# rat.net
KiCad netlist of a schematic drawn in EAGLE
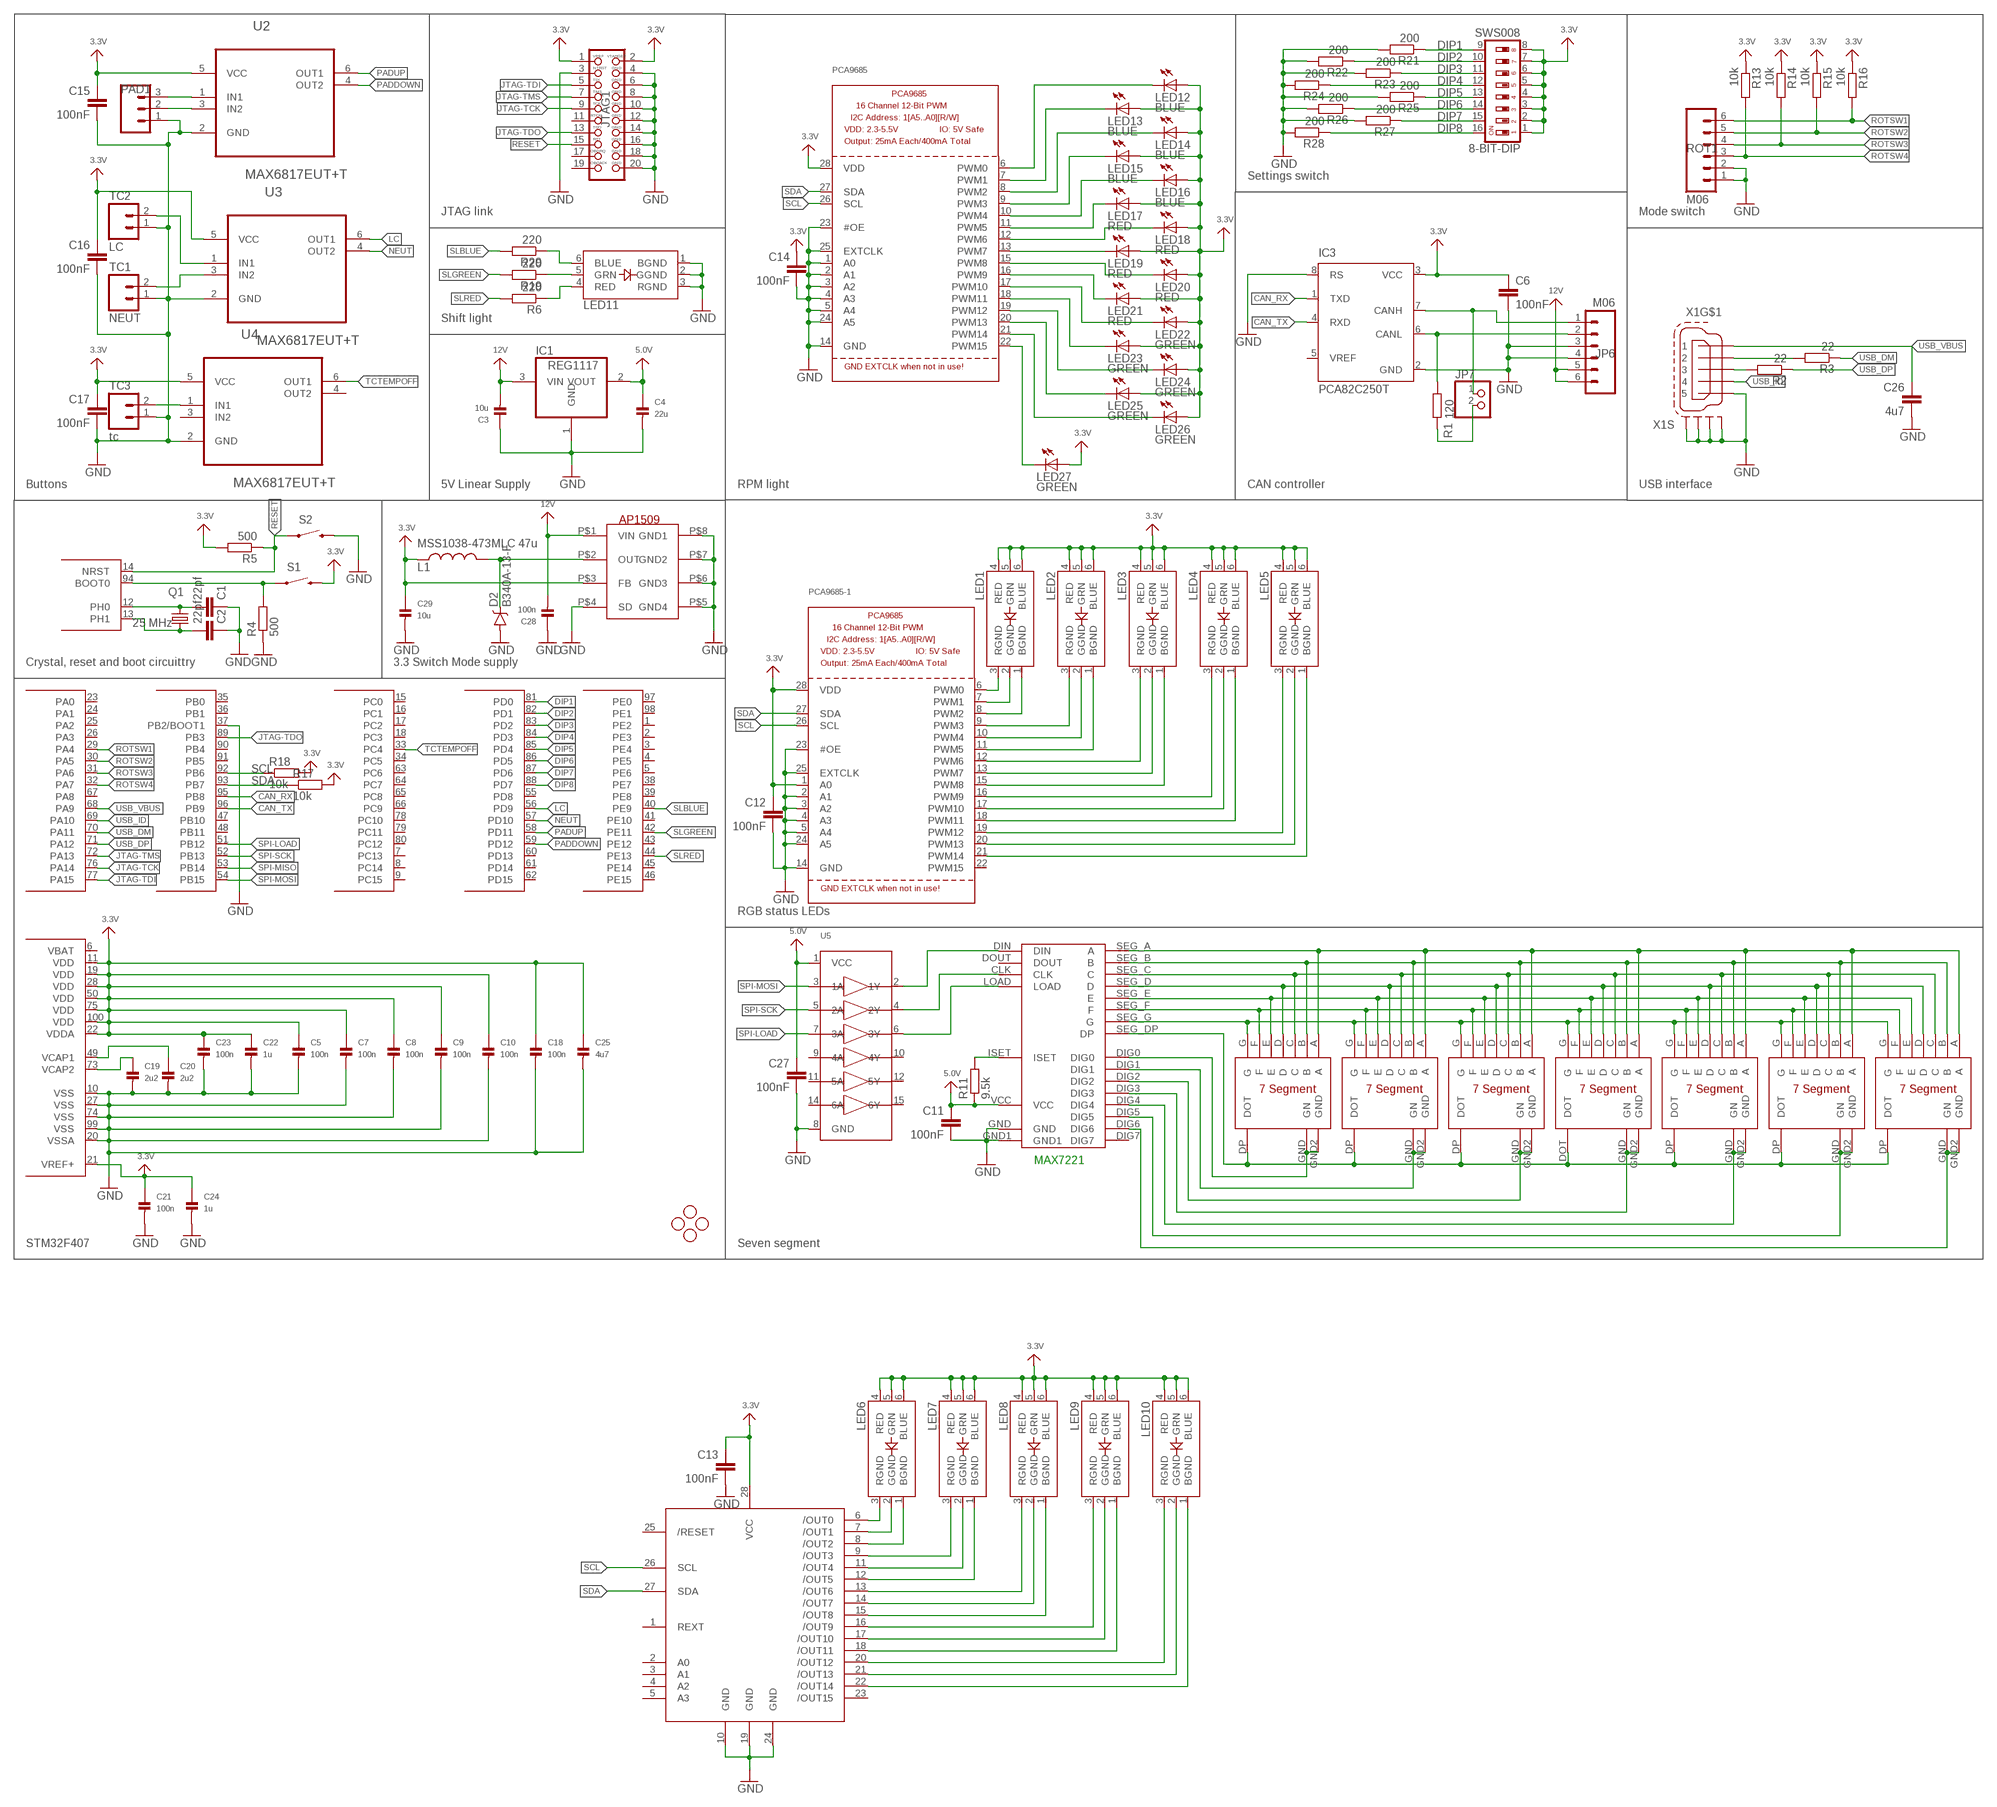
[diagram p0: schematic, sheet 1]

(export (version "E")
  (design (tool "Eeschema 10.0.6"))
  (components
    (comp (ref "8-BIT-DIP")
      (value "SWS008")
      (footprint "eagle-import:SMS-008")
      (libsource (lib "eagle-import") (part "SWS008"))
    )
    (comp (ref "C1")
      (value "22pf")
      (footprint "eagle-import:C0603K")
      (libsource (lib "eagle-import") (part "C-EUC0603K"))
    )
    (comp (ref "C2")
      (value "22pf")
      (footprint "eagle-import:C0603K")
      (libsource (lib "eagle-import") (part "C-EUC0603K"))
    )
    (comp (ref "C3")
      (value "10u")
      (footprint "eagle-import:0805")
      (libsource (lib "eagle-import") (part "CAP_CERAMIC0805"))
    )
    (comp (ref "C4")
      (value "22u")
      (footprint "eagle-import:_0603MP")
      (libsource (lib "eagle-import") (part "CAP_CERAMIC_0603MP"))
    )
    (comp (ref "C5")
      (value "100n")
      (footprint "eagle-import:_0402MP")
      (libsource (lib "eagle-import") (part "CAP_CERAMIC_0402MP"))
    )
    (comp (ref "C6")
      (value "100nF")
      (footprint "eagle-import:C0603K")
      (libsource (lib "eagle-import") (part "C-EUC0603K"))
    )
    (comp (ref "C7")
      (value "100n")
      (footprint "eagle-import:_0402MP")
      (libsource (lib "eagle-import") (part "CAP_CERAMIC_0402MP"))
    )
    (comp (ref "C8")
      (value "100n")
      (footprint "eagle-import:_0402MP")
      (libsource (lib "eagle-import") (part "CAP_CERAMIC_0402MP"))
    )
    (comp (ref "C9")
      (value "100n")
      (footprint "eagle-import:_0402MP")
      (libsource (lib "eagle-import") (part "CAP_CERAMIC_0402MP"))
    )
    (comp (ref "C10")
      (value "100n")
      (footprint "eagle-import:_0402MP")
      (libsource (lib "eagle-import") (part "CAP_CERAMIC_0402MP"))
    )
    (comp (ref "C11")
      (value "100nF")
      (footprint "eagle-import:C0603K")
      (libsource (lib "eagle-import") (part "C-EUC0603K"))
    )
    (comp (ref "C12")
      (value "100nF")
      (footprint "eagle-import:C0603K")
      (libsource (lib "eagle-import") (part "C-EUC0603K"))
    )
    (comp (ref "C13")
      (value "100nF")
      (footprint "eagle-import:C0603K")
      (libsource (lib "eagle-import") (part "C-EUC0603K"))
    )
    (comp (ref "C14")
      (value "100nF")
      (footprint "eagle-import:C0603K")
      (libsource (lib "eagle-import") (part "C-EUC0603K"))
    )
    (comp (ref "C15")
      (value "100nF")
      (footprint "eagle-import:C0603K")
      (libsource (lib "eagle-import") (part "C-EUC0603K"))
    )
    (comp (ref "C16")
      (value "100nF")
      (footprint "eagle-import:C0603K")
      (libsource (lib "eagle-import") (part "C-EUC0603K"))
    )
    (comp (ref "C17")
      (value "100nF")
      (footprint "eagle-import:C0603K")
      (libsource (lib "eagle-import") (part "C-EUC0603K"))
    )
    (comp (ref "C18")
      (value "100n")
      (footprint "eagle-import:_0402MP")
      (libsource (lib "eagle-import") (part "CAP_CERAMIC_0402MP"))
    )
    (comp (ref "C19")
      (value "2u2")
      (footprint "eagle-import:_0402MP")
      (libsource (lib "eagle-import") (part "CAP_CERAMIC_0402MP"))
    )
    (comp (ref "C20")
      (value "2u2")
      (footprint "eagle-import:_0402MP")
      (libsource (lib "eagle-import") (part "CAP_CERAMIC_0402MP"))
    )
    (comp (ref "C21")
      (value "100n")
      (footprint "eagle-import:_0402MP")
      (libsource (lib "eagle-import") (part "CAP_CERAMIC_0402MP"))
    )
    (comp (ref "C22")
      (value "1u")
      (footprint "eagle-import:_0402MP")
      (libsource (lib "eagle-import") (part "CAP_CERAMIC_0402MP"))
    )
    (comp (ref "C23")
      (value "100n")
      (footprint "eagle-import:_0402MP")
      (libsource (lib "eagle-import") (part "CAP_CERAMIC_0402MP"))
    )
    (comp (ref "C24")
      (value "1u")
      (footprint "eagle-import:_0402MP")
      (libsource (lib "eagle-import") (part "CAP_CERAMIC_0402MP"))
    )
    (comp (ref "C25")
      (value "4u7")
      (footprint "eagle-import:_0402MP")
      (libsource (lib "eagle-import") (part "CAP_CERAMIC_0402MP"))
    )
    (comp (ref "C26")
      (value "4u7")
      (footprint "eagle-import:C0603K")
      (libsource (lib "eagle-import") (part "C-EUC0603K"))
    )
    (comp (ref "C27")
      (value "100nF")
      (footprint "eagle-import:C0603K")
      (libsource (lib "eagle-import") (part "C-EUC0603K"))
    )
    (comp (ref "C28")
      (value "100n")
      (footprint "eagle-import:_0603MP")
      (libsource (lib "eagle-import") (part "CAP_CERAMIC_0603MP"))
    )
    (comp (ref "C29")
      (value "10u")
      (footprint "eagle-import:0805")
      (libsource (lib "eagle-import") (part "CAP_CERAMIC0805"))
    )
    (comp (ref "D2")
      (value "B340A-13-F")
      (footprint "eagle-import:SMA-DIODE")
      (libsource (lib "eagle-import") (part "MBRA140"))
    )
    (comp (ref "IC1")
      (value "REG1117")
      (footprint "eagle-import:SOT223")
      (libsource (lib "eagle-import") (part "REG1117"))
    )
    (comp (ref "IC3")
      (value "PCA82C250T")
      (footprint "eagle-import:SO8")
      (libsource (lib "eagle-import") (part "PCA82C250T"))
    )
    (comp (ref "JP2")
      (value "STAND-OFF")
      (footprint "eagle-import:STAND-OFF")
      (libsource (lib "eagle-import") (part "STAND-OFF"))
    )
    (comp (ref "JP3")
      (value "STAND-OFF")
      (footprint "eagle-import:STAND-OFF")
      (libsource (lib "eagle-import") (part "STAND-OFF"))
    )
    (comp (ref "JP4")
      (value "STAND-OFF")
      (footprint "eagle-import:STAND-OFF")
      (libsource (lib "eagle-import") (part "STAND-OFF"))
    )
    (comp (ref "JP5")
      (value "STAND-OFF")
      (footprint "eagle-import:STAND-OFF")
      (libsource (lib "eagle-import") (part "STAND-OFF"))
    )
    (comp (ref "JP6")
      (value "M06")
      (footprint "eagle-import:S6B_PH")
      (libsource (lib "eagle-import") (part "M06"))
    )
    (comp (ref "JP7")
      (value "PINHD-1X2/90")
      (footprint "eagle-import:1X02_90")
      (libsource (lib "eagle-import") (part "PINHD-1X2/90"))
    )
    (comp (ref "JTAG1")
      (value "JTAG-ARMEDGE")
      (footprint "eagle-import:MOLEX20_RIGHTANGLE")
      (libsource (lib "eagle-import") (part "JTAG-ARMEDGE"))
    )
    (comp (ref "L1")
      (value "MSS1038-473MLC 47u")
      (footprint "eagle-import:CDRH125")
      (libsource (lib "eagle-import") (part "INDUCTORPWR"))
    )
    (comp (ref "LED1")
      (value "LED_RGB_PLCC6CREE-CLV6A")
      (footprint "eagle-import:RGBLED_PLCC6")
      (libsource (lib "eagle-import") (part "LED_RGB_PLCC6CREE-CLV6A"))
    )
    (comp (ref "LED2")
      (value "LED_RGB_PLCC6CREE-CLV6A")
      (footprint "eagle-import:RGBLED_PLCC6")
      (libsource (lib "eagle-import") (part "LED_RGB_PLCC6CREE-CLV6A"))
    )
    (comp (ref "LED3")
      (value "LED_RGB_PLCC6CREE-CLV6A")
      (footprint "eagle-import:RGBLED_PLCC6")
      (libsource (lib "eagle-import") (part "LED_RGB_PLCC6CREE-CLV6A"))
    )
    (comp (ref "LED4")
      (value "LED_RGB_PLCC6CREE-CLV6A")
      (footprint "eagle-import:RGBLED_PLCC6")
      (libsource (lib "eagle-import") (part "LED_RGB_PLCC6CREE-CLV6A"))
    )
    (comp (ref "LED5")
      (value "LED_RGB_PLCC6CREE-CLV6A")
      (footprint "eagle-import:RGBLED_PLCC6")
      (libsource (lib "eagle-import") (part "LED_RGB_PLCC6CREE-CLV6A"))
    )
    (comp (ref "LED6")
      (value "LED_RGB_PLCC6CREE-CLV6A")
      (footprint "eagle-import:RGBLED_PLCC6")
      (libsource (lib "eagle-import") (part "LED_RGB_PLCC6CREE-CLV6A"))
    )
    (comp (ref "LED7")
      (value "LED_RGB_PLCC6CREE-CLV6A")
      (footprint "eagle-import:RGBLED_PLCC6")
      (libsource (lib "eagle-import") (part "LED_RGB_PLCC6CREE-CLV6A"))
    )
    (comp (ref "LED8")
      (value "LED_RGB_PLCC6CREE-CLV6A")
      (footprint "eagle-import:RGBLED_PLCC6")
      (libsource (lib "eagle-import") (part "LED_RGB_PLCC6CREE-CLV6A"))
    )
    (comp (ref "LED9")
      (value "LED_RGB_PLCC6CREE-CLV6A")
      (footprint "eagle-import:RGBLED_PLCC6")
      (libsource (lib "eagle-import") (part "LED_RGB_PLCC6CREE-CLV6A"))
    )
    (comp (ref "LED10")
      (value "LED_RGB_PLCC6CREE-CLV6A")
      (footprint "eagle-import:RGBLED_PLCC6")
      (libsource (lib "eagle-import") (part "LED_RGB_PLCC6CREE-CLV6A"))
    )
    (comp (ref "LED11")
      (value "LED_RGB_PLCC6CREE-CLV6A")
      (footprint "eagle-import:RGBLED_PLCC6")
      (libsource (lib "eagle-import") (part "LED_RGB_PLCC6CREE-CLV6A"))
    )
    (comp (ref "LED12")
      (value "BLUE")
      (footprint "eagle-import:1206")
      (libsource (lib "eagle-import") (part "LEDSMT1206"))
    )
    (comp (ref "LED13")
      (value "BLUE")
      (footprint "eagle-import:1206")
      (libsource (lib "eagle-import") (part "LEDSMT1206"))
    )
    (comp (ref "LED14")
      (value "BLUE")
      (footprint "eagle-import:1206")
      (libsource (lib "eagle-import") (part "LEDSMT1206"))
    )
    (comp (ref "LED15")
      (value "BLUE")
      (footprint "eagle-import:1206")
      (libsource (lib "eagle-import") (part "LEDSMT1206"))
    )
    (comp (ref "LED16")
      (value "BLUE")
      (footprint "eagle-import:1206")
      (libsource (lib "eagle-import") (part "LEDSMT1206"))
    )
    (comp (ref "LED17")
      (value "RED")
      (footprint "eagle-import:1206")
      (libsource (lib "eagle-import") (part "LEDSMT1206"))
    )
    (comp (ref "LED18")
      (value "RED")
      (footprint "eagle-import:1206")
      (libsource (lib "eagle-import") (part "LEDSMT1206"))
    )
    (comp (ref "LED19")
      (value "RED")
      (footprint "eagle-import:1206")
      (libsource (lib "eagle-import") (part "LEDSMT1206"))
    )
    (comp (ref "LED20")
      (value "RED")
      (footprint "eagle-import:1206")
      (libsource (lib "eagle-import") (part "LEDSMT1206"))
    )
    (comp (ref "LED21")
      (value "RED")
      (footprint "eagle-import:1206")
      (libsource (lib "eagle-import") (part "LEDSMT1206"))
    )
    (comp (ref "LED22")
      (value "GREEN")
      (footprint "eagle-import:1206")
      (libsource (lib "eagle-import") (part "LEDSMT1206"))
    )
    (comp (ref "LED23")
      (value "GREEN")
      (footprint "eagle-import:1206")
      (libsource (lib "eagle-import") (part "LEDSMT1206"))
    )
    (comp (ref "LED24")
      (value "GREEN")
      (footprint "eagle-import:1206")
      (libsource (lib "eagle-import") (part "LEDSMT1206"))
    )
    (comp (ref "LED25")
      (value "GREEN")
      (footprint "eagle-import:1206")
      (libsource (lib "eagle-import") (part "LEDSMT1206"))
    )
    (comp (ref "LED26")
      (value "GREEN")
      (footprint "eagle-import:1206")
      (libsource (lib "eagle-import") (part "LEDSMT1206"))
    )
    (comp (ref "LED27")
      (value "GREEN")
      (footprint "eagle-import:1206")
      (libsource (lib "eagle-import") (part "LEDSMT1206"))
    )
    (comp (ref "MAX7221")
      (value "MAX7221-SMD")
      (footprint "eagle-import:MAX7221")
      (libsource (lib "eagle-import") (part "MAX7221-SMD"))
    )
    (comp (ref "PAD1")
      (value "M03")
      (footprint "eagle-import:S3B-PH")
      (libsource (lib "eagle-import") (part "M03"))
    )
    (comp (ref "PCA9685")
      (value "PCA9685")
      (footprint "eagle-import:TSSOP28")
      (libsource (lib "eagle-import") (part "PCA9685"))
    )
    (comp (ref "PCA9685-1")
      (value "PCA9685")
      (footprint "eagle-import:TSSOP28")
      (libsource (lib "eagle-import") (part "PCA9685"))
    )
    (comp (ref "Q1")
      (value "25 MHz")
      (footprint "eagle-import:HC49U70")
      (libsource (lib "eagle-import") (part "CRYSTALHC49U70"))
    )
    (comp (ref "R1")
      (value "120")
      (footprint "eagle-import:R0603")
      (libsource (lib "eagle-import") (part "resistor_R-EU_R0603"))
    )
    (comp (ref "R2")
      (value "22")
      (footprint "eagle-import:R0603")
      (libsource (lib "eagle-import") (part "R-EU_R0603"))
    )
    (comp (ref "R3")
      (value "22")
      (footprint "eagle-import:R0603")
      (libsource (lib "eagle-import") (part "R-EU_R0603"))
    )
    (comp (ref "R4")
      (value "500")
      (footprint "eagle-import:R0603")
      (libsource (lib "eagle-import") (part "R-EU_R0603"))
    )
    (comp (ref "R5")
      (value "500")
      (footprint "eagle-import:R0603")
      (libsource (lib "eagle-import") (part "R-EU_R0603"))
    )
    (comp (ref "R6")
      (value "220")
      (footprint "eagle-import:R0603")
      (libsource (lib "eagle-import") (part "R-EU_R0603"))
    )
    (comp (ref "R11")
      (value "9.5k")
      (footprint "eagle-import:R0603")
      (libsource (lib "eagle-import") (part "R-EU_R0603"))
    )
    (comp (ref "R13")
      (value "10k")
      (footprint "eagle-import:R0603")
      (libsource (lib "eagle-import") (part "R-EU_R0603"))
    )
    (comp (ref "R14")
      (value "10k")
      (footprint "eagle-import:R0603")
      (libsource (lib "eagle-import") (part "R-EU_R0603"))
    )
    (comp (ref "R15")
      (value "10k")
      (footprint "eagle-import:R0603")
      (libsource (lib "eagle-import") (part "R-EU_R0603"))
    )
    (comp (ref "R16")
      (value "10k")
      (footprint "eagle-import:R0603")
      (libsource (lib "eagle-import") (part "R-EU_R0603"))
    )
    (comp (ref "R17")
      (value "10k")
      (footprint "eagle-import:R0603")
      (libsource (lib "eagle-import") (part "R-EU_R0603"))
    )
    (comp (ref "R18")
      (value "10k")
      (footprint "eagle-import:R0603")
      (libsource (lib "eagle-import") (part "R-EU_R0603"))
    )
    (comp (ref "R19")
      (value "220")
      (footprint "eagle-import:R0603")
      (libsource (lib "eagle-import") (part "R-EU_R0603"))
    )
    (comp (ref "R21")
      (value "200")
      (footprint "eagle-import:R0603")
      (libsource (lib "eagle-import") (part "R-EU_R0603"))
    )
    (comp (ref "R22")
      (value "200")
      (footprint "eagle-import:R0603")
      (libsource (lib "eagle-import") (part "R-EU_R0603"))
    )
    (comp (ref "R23")
      (value "200")
      (footprint "eagle-import:R0603")
      (libsource (lib "eagle-import") (part "R-EU_R0603"))
    )
    (comp (ref "R24")
      (value "200")
      (footprint "eagle-import:R0603")
      (libsource (lib "eagle-import") (part "R-EU_R0603"))
    )
    (comp (ref "R25")
      (value "200")
      (footprint "eagle-import:R0603")
      (libsource (lib "eagle-import") (part "R-EU_R0603"))
    )
    (comp (ref "R26")
      (value "200")
      (footprint "eagle-import:R0603")
      (libsource (lib "eagle-import") (part "R-EU_R0603"))
    )
    (comp (ref "R27")
      (value "200")
      (footprint "eagle-import:R0603")
      (libsource (lib "eagle-import") (part "R-EU_R0603"))
    )
    (comp (ref "R28")
      (value "200")
      (footprint "eagle-import:R0603")
      (libsource (lib "eagle-import") (part "R-EU_R0603"))
    )
    (comp (ref "R29")
      (value "220")
      (footprint "eagle-import:R0603")
      (libsource (lib "eagle-import") (part "R-EU_R0603"))
    )
    (comp (ref "ROT1")
      (value "M06")
      (footprint "eagle-import:S6B_PH")
      (libsource (lib "eagle-import") (part "M06"))
    )
    (comp (ref "S1")
      (value "SWITCH-MOMENTARY-2-SMD-1101NE")
      (footprint "eagle-import:TACTILE-SWITCH-1101NE")
      (libsource (lib "eagle-import") (part "SWITCH-MOMENTARY-2-SMD-1101NE"))
    )
    (comp (ref "S2")
      (value "SWITCH-MOMENTARY-2-SMD-1101NE")
      (footprint "eagle-import:TACTILE-SWITCH-1101NE")
      (libsource (lib "eagle-import") (part "SWITCH-MOMENTARY-2-SMD-1101NE"))
    )
    (comp (ref "TC1")
      (value "NEUT")
      (footprint "eagle-import:S2B-PH")
      (libsource (lib "eagle-import") (part "M02-JST-2MM-SMT"))
    )
    (comp (ref "TC2")
      (value "LC")
      (footprint "eagle-import:S2B-PH")
      (libsource (lib "eagle-import") (part "M02-JST-2MM-SMT"))
    )
    (comp (ref "TC3")
      (value "tc")
      (footprint "eagle-import:S2B-PH")
      (libsource (lib "eagle-import") (part "M02-JST-2MM-SMT"))
    )
    (comp (ref "U$2")
      (value "REDSEVENSEGMENT")
      (footprint "eagle-import:REDSEGMENT")
      (libsource (lib "eagle-import") (part "REDSEVENSEGMENT"))
    )
    (comp (ref "U$3")
      (value "REDSEVENSEGMENT")
      (footprint "eagle-import:REDSEGMENT")
      (libsource (lib "eagle-import") (part "REDSEVENSEGMENT"))
    )
    (comp (ref "U$4")
      (value "REDSEVENSEGMENT")
      (footprint "eagle-import:REDSEGMENT")
      (libsource (lib "eagle-import") (part "REDSEVENSEGMENT"))
    )
    (comp (ref "U$5")
      (value "BIGSEVENSEGMENT")
      (footprint "eagle-import:BIGSEVENSEGMENT")
      (libsource (lib "eagle-import") (part "BIGSEVENSEGMENT"))
    )
    (comp (ref "U$6")
      (value "REDSEVENSEGMENT")
      (footprint "eagle-import:REDSEGMENT")
      (libsource (lib "eagle-import") (part "REDSEVENSEGMENT"))
    )
    (comp (ref "U$7")
      (value "REDSEVENSEGMENT")
      (footprint "eagle-import:REDSEGMENT")
      (libsource (lib "eagle-import") (part "REDSEVENSEGMENT"))
    )
    (comp (ref "U$8")
      (value "REDSEVENSEGMENT")
      (footprint "eagle-import:REDSEGMENT")
      (libsource (lib "eagle-import") (part "REDSEVENSEGMENT"))
    )
    (comp (ref "U$10")
      (value "AP1509")
      (footprint "eagle-import:SOP-8L")
      (libsource (lib "eagle-import") (part "AP1509"))
    )
    (comp (ref "U$38")
      (value "TLC59116")
      (footprint "eagle-import:TSSOP28")
      (libsource (lib "eagle-import") (part "TLC59116"))
    )
    (comp (ref "U1")
      (value "STM32F4-100")
      (footprint "eagle-import:SQFP-S-14X14-100")
      (libsource (lib "eagle-import") (part "STM32F4-100"))
    )
    (comp (ref "U2")
      (value "MAX6817EUT+T")
      (footprint "eagle-import:SOT95P280X145-6N")
      (libsource (lib "eagle-import") (part "MAX6817EUT+T"))
    )
    (comp (ref "U3")
      (value "MAX6817EUT+T")
      (footprint "eagle-import:SOT95P280X145-6N")
      (libsource (lib "eagle-import") (part "MAX6817EUT+T"))
    )
    (comp (ref "U4")
      (value "MAX6817EUT+T")
      (footprint "eagle-import:SOT95P280X145-6N")
      (libsource (lib "eagle-import") (part "MAX6817EUT+T"))
    )
    (comp (ref "U5")
      (value "74HC4050D")
      (footprint "eagle-import:SOIC16")
      (libsource (lib "eagle-import") (part "74HC4050D"))
    )
    (comp (ref "X1")
      (value "MINI-USB-SCHIELD-32005-201")
      (footprint "eagle-import:32005-201")
      (libsource (lib "eagle-import") (part "MINI-USB-SCHIELD-32005-201"))
    )
  )
  (nets
    (net (code "1") (name "/VBAT") (class "Default")
      (node (ref "U1") (pin "6") (pinfunction "VBAT_6") (pintype "power_in"))
    )
    (net (code "2") (name "3.3V") (class "Default")
      (node (ref "8-BIT-DIP") (pin "1") (pinfunction "1_1") (pintype "passive"))
      (node (ref "8-BIT-DIP") (pin "2") (pinfunction "2_2") (pintype "passive"))
      (node (ref "8-BIT-DIP") (pin "3") (pinfunction "3_3") (pintype "passive"))
      (node (ref "8-BIT-DIP") (pin "4") (pinfunction "4_4") (pintype "passive"))
      (node (ref "8-BIT-DIP") (pin "5") (pinfunction "5_5") (pintype "passive"))
      (node (ref "8-BIT-DIP") (pin "6") (pinfunction "6_6") (pintype "passive"))
      (node (ref "8-BIT-DIP") (pin "7") (pinfunction "7_7") (pintype "passive"))
      (node (ref "8-BIT-DIP") (pin "8") (pinfunction "8_8") (pintype "passive"))
      (node (ref "C10") (pin "1") (pinfunction "P$1_1") (pintype "passive"))
      (node (ref "C12") (pin "1") (pinfunction "1_1") (pintype "passive"))
      (node (ref "C13") (pin "1") (pinfunction "1_1") (pintype "passive"))
      (node (ref "C14") (pin "1") (pinfunction "1_1") (pintype "passive"))
      (node (ref "C15") (pin "1") (pinfunction "1_1") (pintype "passive"))
      (node (ref "C16") (pin "1") (pinfunction "1_1") (pintype "passive"))
      (node (ref "C17") (pin "1") (pinfunction "1_1") (pintype "passive"))
      (node (ref "C18") (pin "1") (pinfunction "P$1_1") (pintype "passive"))
      (node (ref "C21") (pin "1") (pinfunction "P$1_1") (pintype "passive"))
      (node (ref "C22") (pin "1") (pinfunction "P$1_1") (pintype "passive"))
      (node (ref "C23") (pin "1") (pinfunction "P$1_1") (pintype "passive"))
      (node (ref "C24") (pin "1") (pinfunction "P$1_1") (pintype "passive"))
      (node (ref "C25") (pin "1") (pinfunction "P$1_1") (pintype "passive"))
      (node (ref "C29") (pin "1") (pinfunction "P$1_1") (pintype "passive"))
      (node (ref "C5") (pin "1") (pinfunction "P$1_1") (pintype "passive"))
      (node (ref "C6") (pin "1") (pinfunction "1_1") (pintype "passive"))
      (node (ref "C7") (pin "1") (pinfunction "P$1_1") (pintype "passive"))
      (node (ref "C8") (pin "1") (pinfunction "P$1_1") (pintype "passive"))
      (node (ref "C9") (pin "1") (pinfunction "P$1_1") (pintype "passive"))
      (node (ref "IC3") (pin "3") (pinfunction "VCC_3") (pintype "power_in"))
      (node (ref "JTAG1") (pin "1") (pinfunction "1_1") (pintype "passive"))
      (node (ref "JTAG1") (pin "2") (pinfunction "2_2") (pintype "passive"))
      (node (ref "L1") (pin "1") (pinfunction "1_1") (pintype "passive"))
      (node (ref "LED1") (pin "4") (pinfunction "RED_4") (pintype "bidirectional"))
      (node (ref "LED1") (pin "5") (pinfunction "GRN_5") (pintype "bidirectional"))
      (node (ref "LED1") (pin "6") (pinfunction "BLUE_6") (pintype "bidirectional"))
      (node (ref "LED10") (pin "4") (pinfunction "RED_4") (pintype "bidirectional"))
      (node (ref "LED10") (pin "5") (pinfunction "GRN_5") (pintype "bidirectional"))
      (node (ref "LED10") (pin "6") (pinfunction "BLUE_6") (pintype "bidirectional"))
      (node (ref "LED12") (pin "A") (pinfunction "A_A") (pintype "passive"))
      (node (ref "LED13") (pin "A") (pinfunction "A_A") (pintype "passive"))
      (node (ref "LED14") (pin "A") (pinfunction "A_A") (pintype "passive"))
      (node (ref "LED15") (pin "A") (pinfunction "A_A") (pintype "passive"))
      (node (ref "LED16") (pin "A") (pinfunction "A_A") (pintype "passive"))
      (node (ref "LED17") (pin "A") (pinfunction "A_A") (pintype "passive"))
      (node (ref "LED18") (pin "A") (pinfunction "A_A") (pintype "passive"))
      (node (ref "LED19") (pin "A") (pinfunction "A_A") (pintype "passive"))
      (node (ref "LED2") (pin "4") (pinfunction "RED_4") (pintype "bidirectional"))
      (node (ref "LED2") (pin "5") (pinfunction "GRN_5") (pintype "bidirectional"))
      (node (ref "LED2") (pin "6") (pinfunction "BLUE_6") (pintype "bidirectional"))
      (node (ref "LED20") (pin "A") (pinfunction "A_A") (pintype "passive"))
      (node (ref "LED21") (pin "A") (pinfunction "A_A") (pintype "passive"))
      (node (ref "LED22") (pin "A") (pinfunction "A_A") (pintype "passive"))
      (node (ref "LED23") (pin "A") (pinfunction "A_A") (pintype "passive"))
      (node (ref "LED24") (pin "A") (pinfunction "A_A") (pintype "passive"))
      (node (ref "LED25") (pin "A") (pinfunction "A_A") (pintype "passive"))
      (node (ref "LED26") (pin "A") (pinfunction "A_A") (pintype "passive"))
      (node (ref "LED27") (pin "A") (pinfunction "A_A") (pintype "passive"))
      (node (ref "LED3") (pin "4") (pinfunction "RED_4") (pintype "bidirectional"))
      (node (ref "LED3") (pin "5") (pinfunction "GRN_5") (pintype "bidirectional"))
      (node (ref "LED3") (pin "6") (pinfunction "BLUE_6") (pintype "bidirectional"))
      (node (ref "LED4") (pin "4") (pinfunction "RED_4") (pintype "bidirectional"))
      (node (ref "LED4") (pin "5") (pinfunction "GRN_5") (pintype "bidirectional"))
      (node (ref "LED4") (pin "6") (pinfunction "BLUE_6") (pintype "bidirectional"))
      (node (ref "LED5") (pin "4") (pinfunction "RED_4") (pintype "bidirectional"))
      (node (ref "LED5") (pin "5") (pinfunction "GRN_5") (pintype "bidirectional"))
      (node (ref "LED5") (pin "6") (pinfunction "BLUE_6") (pintype "bidirectional"))
      (node (ref "LED6") (pin "4") (pinfunction "RED_4") (pintype "bidirectional"))
      (node (ref "LED6") (pin "5") (pinfunction "GRN_5") (pintype "bidirectional"))
      (node (ref "LED6") (pin "6") (pinfunction "BLUE_6") (pintype "bidirectional"))
      (node (ref "LED7") (pin "4") (pinfunction "RED_4") (pintype "bidirectional"))
      (node (ref "LED7") (pin "5") (pinfunction "GRN_5") (pintype "bidirectional"))
      (node (ref "LED7") (pin "6") (pinfunction "BLUE_6") (pintype "bidirectional"))
      (node (ref "LED8") (pin "4") (pinfunction "RED_4") (pintype "bidirectional"))
      (node (ref "LED8") (pin "5") (pinfunction "GRN_5") (pintype "bidirectional"))
      (node (ref "LED8") (pin "6") (pinfunction "BLUE_6") (pintype "bidirectional"))
      (node (ref "LED9") (pin "4") (pinfunction "RED_4") (pintype "bidirectional"))
      (node (ref "LED9") (pin "5") (pinfunction "GRN_5") (pintype "bidirectional"))
      (node (ref "LED9") (pin "6") (pinfunction "BLUE_6") (pintype "bidirectional"))
      (node (ref "PCA9685") (pin "28") (pinfunction "VDD_28") (pintype "power_in"))
      (node (ref "PCA9685-1") (pin "1") (pinfunction "A0_1") (pintype "bidirectional"))
      (node (ref "PCA9685-1") (pin "28") (pinfunction "VDD_28") (pintype "power_in"))
      (node (ref "R13") (pin "1") (pinfunction "1_1") (pintype "passive"))
      (node (ref "R14") (pin "1") (pinfunction "1_1") (pintype "passive"))
      (node (ref "R15") (pin "1") (pinfunction "1_1") (pintype "passive"))
      (node (ref "R16") (pin "1") (pinfunction "1_1") (pintype "passive"))
      (node (ref "R17") (pin "2") (pinfunction "2_2") (pintype "passive"))
      (node (ref "R18") (pin "2") (pinfunction "2_2") (pintype "passive"))
      (node (ref "R5") (pin "2") (pinfunction "2_2") (pintype "passive"))
      (node (ref "S1") (pin "P$2") (pinfunction "2_P$2") (pintype "passive"))
      (node (ref "U$10") (pin "P$3") (pinfunction "FB_P$3") (pintype "bidirectional"))
      (node (ref "U$38") (pin "28") (pinfunction "VCC_28") (pintype "bidirectional"))
      (node (ref "U1") (pin "100") (pinfunction "VDD_100") (pintype "power_in"))
      (node (ref "U1") (pin "11") (pinfunction "VDD_11") (pintype "power_in"))
      (node (ref "U1") (pin "19") (pinfunction "VDD_19") (pintype "power_in"))
      (node (ref "U1") (pin "21") (pinfunction "VREF+_21") (pintype "passive"))
      (node (ref "U1") (pin "22") (pinfunction "VDDA_22") (pintype "power_in"))
      (node (ref "U1") (pin "28") (pinfunction "VDD_28") (pintype "power_in"))
      (node (ref "U1") (pin "50") (pinfunction "VDD_50") (pintype "power_in"))
      (node (ref "U1") (pin "75") (pinfunction "VDD_75") (pintype "power_in"))
      (node (ref "U2") (pin "5") (pinfunction "VCC_5") (pintype "power_in"))
      (node (ref "U3") (pin "5") (pinfunction "VCC_5") (pintype "power_in"))
      (node (ref "U4") (pin "5") (pinfunction "VCC_5") (pintype "power_in"))
    )
    (net (code "3") (name "5.0V") (class "Default")
      (node (ref "C11") (pin "1") (pinfunction "1_1") (pintype "passive"))
      (node (ref "C27") (pin "1") (pinfunction "1_1") (pintype "passive"))
      (node (ref "C4") (pin "1") (pinfunction "P$1_1") (pintype "passive"))
      (node (ref "IC1") (pin "2") (pinfunction "VOUT_2") (pintype "output"))
      (node (ref "MAX7221") (pin "VCC") (pinfunction "VCC_VCC") (pintype "bidirectional"))
      (node (ref "R11") (pin "1") (pinfunction "1_1") (pintype "passive"))
      (node (ref "U5") (pin "1") (pinfunction "VCC_1") (pintype "bidirectional"))
    )
    (net (code "4") (name "12V") (class "Default")
      (node (ref "C28") (pin "2") (pinfunction "P$2_2") (pintype "passive"))
      (node (ref "C3") (pin "2") (pinfunction "P$2_2") (pintype "passive"))
      (node (ref "IC1") (pin "3") (pinfunction "VIN_3") (pintype "input"))
      (node (ref "JP6") (pin "5") (pinfunction "5_5") (pintype "passive"))
      (node (ref "JP6") (pin "6") (pinfunction "6_6") (pintype "passive"))
      (node (ref "U$10") (pin "P$1") (pinfunction "VIN_P$1") (pintype "bidirectional"))
    )
    (net (code "5") (name "CAN_RX") (class "Default")
      (node (ref "IC3") (pin "1") (pinfunction "TXD_1") (pintype "input"))
      (node (ref "U1") (pin "95") (pinfunction "PB8_95") (pintype "bidirectional"))
    )
    (net (code "6") (name "CAN_TX") (class "Default")
      (node (ref "IC3") (pin "4") (pinfunction "RXD_4") (pintype "output"))
      (node (ref "U1") (pin "96") (pinfunction "PB9_96") (pintype "bidirectional"))
    )
    (net (code "7") (name "DIP1") (class "Default")
      (node (ref "8-BIT-DIP") (pin "9") (pinfunction "9_9") (pintype "passive"))
      (node (ref "R21") (pin "1") (pinfunction "1_1") (pintype "passive"))
      (node (ref "U1") (pin "81") (pinfunction "PD0_81") (pintype "bidirectional"))
    )
    (net (code "8") (name "DIP2") (class "Default")
      (node (ref "8-BIT-DIP") (pin "10") (pinfunction "10_10") (pintype "passive"))
      (node (ref "R22") (pin "1") (pinfunction "1_1") (pintype "passive"))
      (node (ref "U1") (pin "82") (pinfunction "PD1_82") (pintype "bidirectional"))
    )
    (net (code "9") (name "DIP3") (class "Default")
      (node (ref "8-BIT-DIP") (pin "11") (pinfunction "11_11") (pintype "passive"))
      (node (ref "R23") (pin "1") (pinfunction "1_1") (pintype "passive"))
      (node (ref "U1") (pin "83") (pinfunction "PD2_83") (pintype "bidirectional"))
    )
    (net (code "10") (name "DIP4") (class "Default")
      (node (ref "8-BIT-DIP") (pin "12") (pinfunction "12_12") (pintype "passive"))
      (node (ref "R24") (pin "1") (pinfunction "1_1") (pintype "passive"))
      (node (ref "U1") (pin "84") (pinfunction "PD3_84") (pintype "bidirectional"))
    )
    (net (code "11") (name "DIP5") (class "Default")
      (node (ref "8-BIT-DIP") (pin "13") (pinfunction "13_13") (pintype "passive"))
      (node (ref "R25") (pin "1") (pinfunction "1_1") (pintype "passive"))
      (node (ref "U1") (pin "85") (pinfunction "PD4_85") (pintype "bidirectional"))
    )
    (net (code "12") (name "DIP6") (class "Default")
      (node (ref "8-BIT-DIP") (pin "14") (pinfunction "14_14") (pintype "passive"))
      (node (ref "R26") (pin "1") (pinfunction "1_1") (pintype "passive"))
      (node (ref "U1") (pin "86") (pinfunction "PD5_86") (pintype "bidirectional"))
    )
    (net (code "13") (name "DIP7") (class "Default")
      (node (ref "8-BIT-DIP") (pin "15") (pinfunction "15_15") (pintype "passive"))
      (node (ref "R27") (pin "1") (pinfunction "1_1") (pintype "passive"))
      (node (ref "U1") (pin "87") (pinfunction "PD6_87") (pintype "bidirectional"))
    )
    (net (code "14") (name "DIP8") (class "Default")
      (node (ref "8-BIT-DIP") (pin "16") (pinfunction "16_16") (pintype "passive"))
      (node (ref "R28") (pin "1") (pinfunction "1_1") (pintype "passive"))
      (node (ref "U1") (pin "88") (pinfunction "PD7_88") (pintype "bidirectional"))
    )
    (net (code "15") (name "GND") (class "Default")
      (node (ref "C1") (pin "1") (pinfunction "1_1") (pintype "passive"))
      (node (ref "C10") (pin "2") (pinfunction "P$2_2") (pintype "passive"))
      (node (ref "C11") (pin "2") (pinfunction "2_2") (pintype "passive"))
      (node (ref "C12") (pin "2") (pinfunction "2_2") (pintype "passive"))
      (node (ref "C13") (pin "2") (pinfunction "2_2") (pintype "passive"))
      (node (ref "C14") (pin "2") (pinfunction "2_2") (pintype "passive"))
      (node (ref "C15") (pin "2") (pinfunction "2_2") (pintype "passive"))
      (node (ref "C16") (pin "2") (pinfunction "2_2") (pintype "passive"))
      (node (ref "C17") (pin "2") (pinfunction "2_2") (pintype "passive"))
      (node (ref "C18") (pin "2") (pinfunction "P$2_2") (pintype "passive"))
      (node (ref "C19") (pin "2") (pinfunction "P$2_2") (pintype "passive"))
      (node (ref "C2") (pin "1") (pinfunction "1_1") (pintype "passive"))
      (node (ref "C20") (pin "2") (pinfunction "P$2_2") (pintype "passive"))
      (node (ref "C21") (pin "2") (pinfunction "P$2_2") (pintype "passive"))
      (node (ref "C22") (pin "2") (pinfunction "P$2_2") (pintype "passive"))
      (node (ref "C23") (pin "2") (pinfunction "P$2_2") (pintype "passive"))
      (node (ref "C24") (pin "2") (pinfunction "P$2_2") (pintype "passive"))
      (node (ref "C25") (pin "2") (pinfunction "P$2_2") (pintype "passive"))
      (node (ref "C26") (pin "2") (pinfunction "2_2") (pintype "passive"))
      (node (ref "C27") (pin "2") (pinfunction "2_2") (pintype "passive"))
      (node (ref "C28") (pin "1") (pinfunction "P$1_1") (pintype "passive"))
      (node (ref "C29") (pin "2") (pinfunction "P$2_2") (pintype "passive"))
      (node (ref "C3") (pin "1") (pinfunction "P$1_1") (pintype "passive"))
      (node (ref "C4") (pin "2") (pinfunction "P$2_2") (pintype "passive"))
      (node (ref "C5") (pin "2") (pinfunction "P$2_2") (pintype "passive"))
      (node (ref "C6") (pin "2") (pinfunction "2_2") (pintype "passive"))
      (node (ref "C7") (pin "2") (pinfunction "P$2_2") (pintype "passive"))
      (node (ref "C8") (pin "2") (pinfunction "P$2_2") (pintype "passive"))
      (node (ref "C9") (pin "2") (pinfunction "P$2_2") (pintype "passive"))
      (node (ref "D2") (pin "A") (pinfunction "A_A") (pintype "passive"))
      (node (ref "IC1") (pin "1") (pinfunction "GND_1") (pintype "power_in"))
      (node (ref "IC3") (pin "2") (pinfunction "GND_2") (pintype "power_in"))
      (node (ref "IC3") (pin "8") (pinfunction "RS_8") (pintype "input"))
      (node (ref "JP6") (pin "3") (pinfunction "3_3") (pintype "passive"))
      (node (ref "JP6") (pin "4") (pinfunction "4_4") (pintype "passive"))
      (node (ref "JTAG1") (pin "10") (pinfunction "10_10") (pintype "passive"))
      (node (ref "JTAG1") (pin "12") (pinfunction "12_12") (pintype "passive"))
      (node (ref "JTAG1") (pin "14") (pinfunction "14_14") (pintype "passive"))
      (node (ref "JTAG1") (pin "16") (pinfunction "16_16") (pintype "passive"))
      (node (ref "JTAG1") (pin "18") (pinfunction "18_18") (pintype "passive"))
      (node (ref "JTAG1") (pin "20") (pinfunction "20_20") (pintype "passive"))
      (node (ref "JTAG1") (pin "3") (pinfunction "3_3") (pintype "passive"))
      (node (ref "JTAG1") (pin "4") (pinfunction "4_4") (pintype "passive"))
      (node (ref "JTAG1") (pin "6") (pinfunction "6_6") (pintype "passive"))
      (node (ref "JTAG1") (pin "8") (pinfunction "8_8") (pintype "passive"))
      (node (ref "LED11") (pin "1") (pinfunction "BGND_1") (pintype "power_in"))
      (node (ref "LED11") (pin "2") (pinfunction "GGND_2") (pintype "power_in"))
      (node (ref "LED11") (pin "3") (pinfunction "RGND_3") (pintype "power_in"))
      (node (ref "MAX7221") (pin "GND") (pinfunction "GND_GND") (pintype "bidirectional"))
      (node (ref "MAX7221") (pin "GND1") (pinfunction "GND1_GND1") (pintype "bidirectional"))
      (node (ref "PAD1") (pin "1") (pinfunction "1_1") (pintype "passive"))
      (node (ref "PCA9685") (pin "1") (pinfunction "A0_1") (pintype "bidirectional"))
      (node (ref "PCA9685") (pin "14") (pinfunction "GND_14") (pintype "power_in"))
      (node (ref "PCA9685") (pin "2") (pinfunction "A1_2") (pintype "bidirectional"))
      (node (ref "PCA9685") (pin "23") (pinfunction "#OE_23") (pintype "input"))
      (node (ref "PCA9685") (pin "24") (pinfunction "A5_24") (pintype "bidirectional"))
      (node (ref "PCA9685") (pin "25") (pinfunction "EXTCLK_25") (pintype "input"))
      (node (ref "PCA9685") (pin "3") (pinfunction "A2_3") (pintype "bidirectional"))
      (node (ref "PCA9685") (pin "4") (pinfunction "A3_4") (pintype "bidirectional"))
      (node (ref "PCA9685") (pin "5") (pinfunction "A4_5") (pintype "bidirectional"))
      (node (ref "PCA9685-1") (pin "14") (pinfunction "GND_14") (pintype "power_in"))
      (node (ref "PCA9685-1") (pin "2") (pinfunction "A1_2") (pintype "bidirectional"))
      (node (ref "PCA9685-1") (pin "23") (pinfunction "#OE_23") (pintype "input"))
      (node (ref "PCA9685-1") (pin "24") (pinfunction "A5_24") (pintype "bidirectional"))
      (node (ref "PCA9685-1") (pin "25") (pinfunction "EXTCLK_25") (pintype "input"))
      (node (ref "PCA9685-1") (pin "3") (pinfunction "A2_3") (pintype "bidirectional"))
      (node (ref "PCA9685-1") (pin "4") (pinfunction "A3_4") (pintype "bidirectional"))
      (node (ref "PCA9685-1") (pin "5") (pinfunction "A4_5") (pintype "bidirectional"))
      (node (ref "R21") (pin "2") (pinfunction "2_2") (pintype "passive"))
      (node (ref "R22") (pin "2") (pinfunction "2_2") (pintype "passive"))
      (node (ref "R23") (pin "2") (pinfunction "2_2") (pintype "passive"))
      (node (ref "R24") (pin "2") (pinfunction "2_2") (pintype "passive"))
      (node (ref "R25") (pin "2") (pinfunction "2_2") (pintype "passive"))
      (node (ref "R26") (pin "2") (pinfunction "2_2") (pintype "passive"))
      (node (ref "R27") (pin "2") (pinfunction "2_2") (pintype "passive"))
      (node (ref "R28") (pin "2") (pinfunction "2_2") (pintype "passive"))
      (node (ref "R4") (pin "1") (pinfunction "1_1") (pintype "passive"))
      (node (ref "ROT1") (pin "1") (pinfunction "1_1") (pintype "passive"))
      (node (ref "ROT1") (pin "2") (pinfunction "2_2") (pintype "passive"))
      (node (ref "S2") (pin "P$2") (pinfunction "2_P$2") (pintype "passive"))
      (node (ref "TC1") (pin "1") (pinfunction "1_1") (pintype "passive"))
      (node (ref "TC2") (pin "1") (pinfunction "1_1") (pintype "passive"))
      (node (ref "TC3") (pin "1") (pinfunction "1_1") (pintype "passive"))
      (node (ref "U$10") (pin "P$4") (pinfunction "SD_P$4") (pintype "bidirectional"))
      (node (ref "U$10") (pin "P$5") (pinfunction "GND4_P$5") (pintype "bidirectional"))
      (node (ref "U$10") (pin "P$6") (pinfunction "GND3_P$6") (pintype "bidirectional"))
      (node (ref "U$10") (pin "P$7") (pinfunction "GND2_P$7") (pintype "bidirectional"))
      (node (ref "U$10") (pin "P$8") (pinfunction "GND1_P$8") (pintype "bidirectional"))
      (node (ref "U$38") (pin "10") (pinfunction "GND_10") (pintype "bidirectional"))
      (node (ref "U$38") (pin "19") (pinfunction "GND_19") (pintype "bidirectional"))
      (node (ref "U$38") (pin "24") (pinfunction "GND_24") (pintype "bidirectional"))
      (node (ref "U1") (pin "10") (pinfunction "VSS_10") (pintype "power_in"))
      (node (ref "U1") (pin "20") (pinfunction "VSSA_20") (pintype "power_in"))
      (node (ref "U1") (pin "27") (pinfunction "VSS_27") (pintype "power_in"))
      (node (ref "U1") (pin "37") (pinfunction "PB2/BOOT1_37") (pintype "bidirectional"))
      (node (ref "U1") (pin "74") (pinfunction "VSS_74") (pintype "power_in"))
      (node (ref "U1") (pin "99") (pinfunction "VSS_99") (pintype "power_in"))
      (node (ref "U2") (pin "2") (pinfunction "GND_2") (pintype "passive"))
      (node (ref "U3") (pin "2") (pinfunction "GND_2") (pintype "passive"))
      (node (ref "U4") (pin "2") (pinfunction "GND_2") (pintype "passive"))
      (node (ref "U5") (pin "8") (pinfunction "GND_8") (pintype "bidirectional"))
      (node (ref "X1") (pin "5") (pinfunction "5_5") (pintype "passive"))
      (node (ref "X1") (pin "M1") (pinfunction "S1_M1") (pintype "passive"))
      (node (ref "X1") (pin "M2") (pinfunction "S2_M2") (pintype "passive"))
      (node (ref "X1") (pin "M3") (pinfunction "S3_M3") (pintype "passive"))
      (node (ref "X1") (pin "M4") (pinfunction "S4_M4") (pintype "passive"))
    )
    (net (code "16") (name "JTAG-TCK") (class "Default")
      (node (ref "JTAG1") (pin "9") (pinfunction "9_9") (pintype "passive"))
      (node (ref "U1") (pin "76") (pinfunction "PA14_76") (pintype "bidirectional"))
    )
    (net (code "17") (name "JTAG-TDI") (class "Default")
      (node (ref "JTAG1") (pin "5") (pinfunction "5_5") (pintype "passive"))
      (node (ref "U1") (pin "77") (pinfunction "PA15_77") (pintype "bidirectional"))
    )
    (net (code "18") (name "JTAG-TDO") (class "Default")
      (node (ref "JTAG1") (pin "13") (pinfunction "13_13") (pintype "passive"))
      (node (ref "U1") (pin "89") (pinfunction "PB3_89") (pintype "bidirectional"))
    )
    (net (code "19") (name "JTAG-TMS") (class "Default")
      (node (ref "JTAG1") (pin "7") (pinfunction "7_7") (pintype "passive"))
      (node (ref "U1") (pin "72") (pinfunction "PA13_72") (pintype "bidirectional"))
    )
    (net (code "20") (name "LC") (class "Default")
      (node (ref "U1") (pin "56") (pinfunction "PD9_56") (pintype "bidirectional"))
      (node (ref "U3") (pin "6") (pinfunction "OUT1_6") (pintype "output"))
    )
    (net (code "21") (name "NEUT") (class "Default")
      (node (ref "U1") (pin "57") (pinfunction "PD10_57") (pintype "bidirectional"))
      (node (ref "U3") (pin "4") (pinfunction "OUT2_4") (pintype "output"))
    )
    (net (code "22") (name "Net-(C19-P$1)") (class "Default")
      (node (ref "C19") (pin "1") (pinfunction "P$1_1") (pintype "passive"))
      (node (ref "U1") (pin "73") (pinfunction "VCAP2_73") (pintype "passive"))
    )
    (net (code "23") (name "Net-(C20-P$1)") (class "Default")
      (node (ref "C20") (pin "1") (pinfunction "P$1_1") (pintype "passive"))
      (node (ref "U1") (pin "49") (pinfunction "VCAP1_49") (pintype "passive"))
    )
    (net (code "24") (name "Net-(IC3-CANH)") (class "Default")
      (node (ref "IC3") (pin "7") (pinfunction "CANH_7") (pintype "bidirectional"))
      (node (ref "JP6") (pin "1") (pinfunction "1_1") (pintype "passive"))
      (node (ref "JP7") (pin "1") (pinfunction "1_1") (pintype "passive"))
    )
    (net (code "25") (name "Net-(IC3-CANL)") (class "Default")
      (node (ref "IC3") (pin "6") (pinfunction "CANL_6") (pintype "bidirectional"))
      (node (ref "JP6") (pin "2") (pinfunction "2_2") (pintype "passive"))
      (node (ref "R1") (pin "1") (pinfunction "1_1") (pintype "passive"))
    )
    (net (code "26") (name "Net-(JP7-Pad2)") (class "Default")
      (node (ref "JP7") (pin "2") (pinfunction "2_2") (pintype "passive"))
      (node (ref "R1") (pin "2") (pinfunction "2_2") (pintype "passive"))
    )
    (net (code "27") (name "Net-(LED1-BGND)") (class "Default")
      (node (ref "LED1") (pin "1") (pinfunction "BGND_1") (pintype "power_in"))
      (node (ref "PCA9685-1") (pin "8") (pinfunction "PWM2_8") (pintype "output"))
    )
    (net (code "28") (name "Net-(LED1-GGND)") (class "Default")
      (node (ref "LED1") (pin "2") (pinfunction "GGND_2") (pintype "power_in"))
      (node (ref "PCA9685-1") (pin "7") (pinfunction "PWM1_7") (pintype "output"))
    )
    (net (code "29") (name "Net-(LED1-RGND)") (class "Default")
      (node (ref "LED1") (pin "3") (pinfunction "RGND_3") (pintype "power_in"))
      (node (ref "PCA9685-1") (pin "6") (pinfunction "PWM0_6") (pintype "output"))
    )
    (net (code "30") (name "Net-(LED2-BGND)") (class "Default")
      (node (ref "LED2") (pin "1") (pinfunction "BGND_1") (pintype "power_in"))
      (node (ref "PCA9685-1") (pin "11") (pinfunction "PWM5_11") (pintype "output"))
    )
    (net (code "31") (name "Net-(LED2-GGND)") (class "Default")
      (node (ref "LED2") (pin "2") (pinfunction "GGND_2") (pintype "power_in"))
      (node (ref "PCA9685-1") (pin "10") (pinfunction "PWM4_10") (pintype "output"))
    )
    (net (code "32") (name "Net-(LED2-RGND)") (class "Default")
      (node (ref "LED2") (pin "3") (pinfunction "RGND_3") (pintype "power_in"))
      (node (ref "PCA9685-1") (pin "9") (pinfunction "PWM3_9") (pintype "output"))
    )
    (net (code "33") (name "Net-(LED3-BGND)") (class "Default")
      (node (ref "LED3") (pin "1") (pinfunction "BGND_1") (pintype "power_in"))
      (node (ref "PCA9685-1") (pin "15") (pinfunction "PWM8_15") (pintype "output"))
    )
    (net (code "34") (name "Net-(LED3-GGND)") (class "Default")
      (node (ref "LED3") (pin "2") (pinfunction "GGND_2") (pintype "power_in"))
      (node (ref "PCA9685-1") (pin "13") (pinfunction "PWM7_13") (pintype "output"))
    )
    (net (code "35") (name "Net-(LED3-RGND)") (class "Default")
      (node (ref "LED3") (pin "3") (pinfunction "RGND_3") (pintype "power_in"))
      (node (ref "PCA9685-1") (pin "12") (pinfunction "PWM6_12") (pintype "output"))
    )
    (net (code "36") (name "Net-(LED4-BGND)") (class "Default")
      (node (ref "LED4") (pin "1") (pinfunction "BGND_1") (pintype "power_in"))
      (node (ref "PCA9685-1") (pin "18") (pinfunction "PWM11_18") (pintype "output"))
    )
    (net (code "37") (name "Net-(LED4-GGND)") (class "Default")
      (node (ref "LED4") (pin "2") (pinfunction "GGND_2") (pintype "power_in"))
      (node (ref "PCA9685-1") (pin "17") (pinfunction "PWM10_17") (pintype "output"))
    )
    (net (code "38") (name "Net-(LED4-RGND)") (class "Default")
      (node (ref "LED4") (pin "3") (pinfunction "RGND_3") (pintype "power_in"))
      (node (ref "PCA9685-1") (pin "16") (pinfunction "PWM9_16") (pintype "output"))
    )
    (net (code "39") (name "Net-(LED5-BGND)") (class "Default")
      (node (ref "LED5") (pin "1") (pinfunction "BGND_1") (pintype "power_in"))
      (node (ref "PCA9685-1") (pin "21") (pinfunction "PWM14_21") (pintype "output"))
    )
    (net (code "40") (name "Net-(LED5-GGND)") (class "Default")
      (node (ref "LED5") (pin "2") (pinfunction "GGND_2") (pintype "power_in"))
      (node (ref "PCA9685-1") (pin "20") (pinfunction "PWM13_20") (pintype "output"))
    )
    (net (code "41") (name "Net-(LED5-RGND)") (class "Default")
      (node (ref "LED5") (pin "3") (pinfunction "RGND_3") (pintype "power_in"))
      (node (ref "PCA9685-1") (pin "19") (pinfunction "PWM12_19") (pintype "output"))
    )
    (net (code "42") (name "Net-(LED6-BGND)") (class "Default")
      (node (ref "LED6") (pin "1") (pinfunction "BGND_1") (pintype "power_in"))
      (node (ref "U$38") (pin "8") (pinfunction "/OUT2_8") (pintype "bidirectional"))
    )
    (net (code "43") (name "Net-(LED6-GGND)") (class "Default")
      (node (ref "LED6") (pin "2") (pinfunction "GGND_2") (pintype "power_in"))
      (node (ref "U$38") (pin "7") (pinfunction "/OUT1_7") (pintype "bidirectional"))
    )
    (net (code "44") (name "Net-(LED6-RGND)") (class "Default")
      (node (ref "LED6") (pin "3") (pinfunction "RGND_3") (pintype "power_in"))
      (node (ref "U$38") (pin "6") (pinfunction "/OUT0_6") (pintype "bidirectional"))
    )
    (net (code "45") (name "Net-(LED7-BGND)") (class "Default")
      (node (ref "LED7") (pin "1") (pinfunction "BGND_1") (pintype "power_in"))
      (node (ref "U$38") (pin "12") (pinfunction "/OUT5_12") (pintype "bidirectional"))
    )
    (net (code "46") (name "Net-(LED7-GGND)") (class "Default")
      (node (ref "LED7") (pin "2") (pinfunction "GGND_2") (pintype "power_in"))
      (node (ref "U$38") (pin "11") (pinfunction "/OUT4_11") (pintype "bidirectional"))
    )
    (net (code "47") (name "Net-(LED7-RGND)") (class "Default")
      (node (ref "LED7") (pin "3") (pinfunction "RGND_3") (pintype "power_in"))
      (node (ref "U$38") (pin "9") (pinfunction "/OUT3_9") (pintype "bidirectional"))
    )
    (net (code "48") (name "Net-(LED8-BGND)") (class "Default")
      (node (ref "LED8") (pin "1") (pinfunction "BGND_1") (pintype "power_in"))
      (node (ref "U$38") (pin "15") (pinfunction "/OUT8_15") (pintype "bidirectional"))
    )
    (net (code "49") (name "Net-(LED8-GGND)") (class "Default")
      (node (ref "LED8") (pin "2") (pinfunction "GGND_2") (pintype "power_in"))
      (node (ref "U$38") (pin "14") (pinfunction "/OUT7_14") (pintype "bidirectional"))
    )
    (net (code "50") (name "Net-(LED8-RGND)") (class "Default")
      (node (ref "LED8") (pin "3") (pinfunction "RGND_3") (pintype "power_in"))
      (node (ref "U$38") (pin "13") (pinfunction "/OUT6_13") (pintype "bidirectional"))
    )
    (net (code "51") (name "Net-(LED9-BGND)") (class "Default")
      (node (ref "LED9") (pin "1") (pinfunction "BGND_1") (pintype "power_in"))
      (node (ref "U$38") (pin "18") (pinfunction "/OUT11_18") (pintype "bidirectional"))
    )
    (net (code "52") (name "Net-(LED9-GGND)") (class "Default")
      (node (ref "LED9") (pin "2") (pinfunction "GGND_2") (pintype "power_in"))
      (node (ref "U$38") (pin "17") (pinfunction "/OUT10_17") (pintype "bidirectional"))
    )
    (net (code "53") (name "Net-(LED9-RGND)") (class "Default")
      (node (ref "LED9") (pin "3") (pinfunction "RGND_3") (pintype "power_in"))
      (node (ref "U$38") (pin "16") (pinfunction "/OUT9_16") (pintype "bidirectional"))
    )
    (net (code "54") (name "Net-(LED10-BGND)") (class "Default")
      (node (ref "LED10") (pin "1") (pinfunction "BGND_1") (pintype "power_in"))
      (node (ref "U$38") (pin "22") (pinfunction "/OUT14_22") (pintype "bidirectional"))
    )
    (net (code "55") (name "Net-(LED10-GGND)") (class "Default")
      (node (ref "LED10") (pin "2") (pinfunction "GGND_2") (pintype "power_in"))
      (node (ref "U$38") (pin "21") (pinfunction "/OUT13_21") (pintype "bidirectional"))
    )
    (net (code "56") (name "Net-(LED10-RGND)") (class "Default")
      (node (ref "LED10") (pin "3") (pinfunction "RGND_3") (pintype "power_in"))
      (node (ref "U$38") (pin "20") (pinfunction "/OUT12_20") (pintype "bidirectional"))
    )
    (net (code "57") (name "Net-(LED11-BLUE)") (class "Default")
      (node (ref "LED11") (pin "6") (pinfunction "BLUE_6") (pintype "bidirectional"))
      (node (ref "R29") (pin "1") (pinfunction "1_1") (pintype "passive"))
    )
    (net (code "58") (name "Net-(LED11-GRN)") (class "Default")
      (node (ref "LED11") (pin "5") (pinfunction "GRN_5") (pintype "bidirectional"))
      (node (ref "R19") (pin "1") (pinfunction "1_1") (pintype "passive"))
    )
    (net (code "59") (name "Net-(LED11-RED)") (class "Default")
      (node (ref "LED11") (pin "4") (pinfunction "RED_4") (pintype "bidirectional"))
      (node (ref "R6") (pin "1") (pinfunction "1_1") (pintype "passive"))
    )
    (net (code "60") (name "Net-(MAX7221-A)") (class "Default")
      (node (ref "MAX7221") (pin "SEG_A") (pinfunction "A_SEG_A") (pintype "bidirectional"))
      (node (ref "U$2") (pin "A") (pinfunction "A_A") (pintype "bidirectional"))
      (node (ref "U$3") (pin "A") (pinfunction "A_A") (pintype "bidirectional"))
      (node (ref "U$4") (pin "A") (pinfunction "A_A") (pintype "bidirectional"))
      (node (ref "U$5") (pin "A") (pinfunction "A_A") (pintype "bidirectional"))
      (node (ref "U$6") (pin "A") (pinfunction "A_A") (pintype "bidirectional"))
      (node (ref "U$7") (pin "A") (pinfunction "A_A") (pintype "bidirectional"))
      (node (ref "U$8") (pin "A") (pinfunction "A_A") (pintype "bidirectional"))
    )
    (net (code "61") (name "Net-(MAX7221-B)") (class "Default")
      (node (ref "MAX7221") (pin "SEG_B") (pinfunction "B_SEG_B") (pintype "bidirectional"))
      (node (ref "U$2") (pin "B") (pinfunction "B_B") (pintype "bidirectional"))
      (node (ref "U$3") (pin "B") (pinfunction "B_B") (pintype "bidirectional"))
      (node (ref "U$4") (pin "B") (pinfunction "B_B") (pintype "bidirectional"))
      (node (ref "U$5") (pin "B") (pinfunction "B_B") (pintype "bidirectional"))
      (node (ref "U$6") (pin "B") (pinfunction "B_B") (pintype "bidirectional"))
      (node (ref "U$7") (pin "B") (pinfunction "B_B") (pintype "bidirectional"))
      (node (ref "U$8") (pin "B") (pinfunction "B_B") (pintype "bidirectional"))
    )
    (net (code "62") (name "Net-(MAX7221-C)") (class "Default")
      (node (ref "MAX7221") (pin "SEG_C") (pinfunction "C_SEG_C") (pintype "bidirectional"))
      (node (ref "U$2") (pin "C") (pinfunction "C_C") (pintype "bidirectional"))
      (node (ref "U$3") (pin "C") (pinfunction "C_C") (pintype "bidirectional"))
      (node (ref "U$4") (pin "C") (pinfunction "C_C") (pintype "bidirectional"))
      (node (ref "U$5") (pin "C") (pinfunction "C_C") (pintype "bidirectional"))
      (node (ref "U$6") (pin "C") (pinfunction "C_C") (pintype "bidirectional"))
      (node (ref "U$7") (pin "C") (pinfunction "C_C") (pintype "bidirectional"))
      (node (ref "U$8") (pin "C") (pinfunction "C_C") (pintype "bidirectional"))
    )
    (net (code "63") (name "Net-(MAX7221-D)") (class "Default")
      (node (ref "MAX7221") (pin "SEG_D") (pinfunction "D_SEG_D") (pintype "bidirectional"))
      (node (ref "U$2") (pin "D") (pinfunction "D_D") (pintype "bidirectional"))
      (node (ref "U$3") (pin "D") (pinfunction "D_D") (pintype "bidirectional"))
      (node (ref "U$4") (pin "D") (pinfunction "D_D") (pintype "bidirectional"))
      (node (ref "U$5") (pin "D") (pinfunction "D_D") (pintype "bidirectional"))
      (node (ref "U$6") (pin "D") (pinfunction "D_D") (pintype "bidirectional"))
      (node (ref "U$7") (pin "D") (pinfunction "D_D") (pintype "bidirectional"))
      (node (ref "U$8") (pin "D") (pinfunction "D_D") (pintype "bidirectional"))
    )
    (net (code "64") (name "Net-(MAX7221-DP)") (class "Default")
      (node (ref "MAX7221") (pin "SEG_DP") (pinfunction "DP_SEG_DP") (pintype "bidirectional"))
      (node (ref "U$2") (pin "DP") (pinfunction "DOT_DP") (pintype "bidirectional"))
      (node (ref "U$3") (pin "DP") (pinfunction "DOT_DP") (pintype "bidirectional"))
      (node (ref "U$4") (pin "DP") (pinfunction "DOT_DP") (pintype "bidirectional"))
      (node (ref "U$5") (pin "DOT") (pinfunction "DOT_DOT") (pintype "bidirectional"))
      (node (ref "U$6") (pin "DP") (pinfunction "DOT_DP") (pintype "bidirectional"))
      (node (ref "U$7") (pin "DP") (pinfunction "DOT_DP") (pintype "bidirectional"))
      (node (ref "U$8") (pin "DP") (pinfunction "DOT_DP") (pintype "bidirectional"))
    )
    (net (code "65") (name "Net-(MAX7221-E)") (class "Default")
      (node (ref "MAX7221") (pin "SEG_E") (pinfunction "E_SEG_E") (pintype "bidirectional"))
      (node (ref "U$2") (pin "E") (pinfunction "E_E") (pintype "bidirectional"))
      (node (ref "U$3") (pin "E") (pinfunction "E_E") (pintype "bidirectional"))
      (node (ref "U$4") (pin "E") (pinfunction "E_E") (pintype "bidirectional"))
      (node (ref "U$5") (pin "E") (pinfunction "E_E") (pintype "bidirectional"))
      (node (ref "U$6") (pin "E") (pinfunction "E_E") (pintype "bidirectional"))
      (node (ref "U$7") (pin "E") (pinfunction "E_E") (pintype "bidirectional"))
      (node (ref "U$8") (pin "E") (pinfunction "E_E") (pintype "bidirectional"))
    )
    (net (code "66") (name "Net-(MAX7221-F)") (class "Default")
      (node (ref "MAX7221") (pin "SEG_F") (pinfunction "F_SEG_F") (pintype "bidirectional"))
      (node (ref "U$2") (pin "F") (pinfunction "F_F") (pintype "bidirectional"))
      (node (ref "U$3") (pin "F") (pinfunction "F_F") (pintype "bidirectional"))
      (node (ref "U$4") (pin "F") (pinfunction "F_F") (pintype "bidirectional"))
      (node (ref "U$5") (pin "F") (pinfunction "F_F") (pintype "bidirectional"))
      (node (ref "U$6") (pin "F") (pinfunction "F_F") (pintype "bidirectional"))
      (node (ref "U$7") (pin "F") (pinfunction "F_F") (pintype "bidirectional"))
      (node (ref "U$8") (pin "F") (pinfunction "F_F") (pintype "bidirectional"))
    )
    (net (code "67") (name "Net-(MAX7221-G)") (class "Default")
      (node (ref "MAX7221") (pin "SEG_G") (pinfunction "G_SEG_G") (pintype "bidirectional"))
      (node (ref "U$2") (pin "G") (pinfunction "G_G") (pintype "bidirectional"))
      (node (ref "U$3") (pin "G") (pinfunction "G_G") (pintype "bidirectional"))
      (node (ref "U$4") (pin "G") (pinfunction "G_G") (pintype "bidirectional"))
      (node (ref "U$5") (pin "G") (pinfunction "G_G") (pintype "bidirectional"))
      (node (ref "U$6") (pin "G") (pinfunction "G_G") (pintype "bidirectional"))
      (node (ref "U$7") (pin "G") (pinfunction "G_G") (pintype "bidirectional"))
      (node (ref "U$8") (pin "G") (pinfunction "G_G") (pintype "bidirectional"))
    )
    (net (code "68") (name "Net-(MAX7221-PadISET)") (class "Default")
      (node (ref "MAX7221") (pin "ISET") (pinfunction "ISET_ISET") (pintype "bidirectional"))
      (node (ref "R11") (pin "2") (pinfunction "2_2") (pintype "passive"))
    )
    (net (code "69") (name "Net-(PCA9685-PWM0)") (class "Default")
      (node (ref "LED12") (pin "C") (pinfunction "C_C") (pintype "passive"))
      (node (ref "PCA9685") (pin "6") (pinfunction "PWM0_6") (pintype "output"))
    )
    (net (code "70") (name "Net-(PCA9685-PWM1)") (class "Default")
      (node (ref "LED13") (pin "C") (pinfunction "C_C") (pintype "passive"))
      (node (ref "PCA9685") (pin "7") (pinfunction "PWM1_7") (pintype "output"))
    )
    (net (code "71") (name "Net-(PCA9685-PWM2)") (class "Default")
      (node (ref "LED14") (pin "C") (pinfunction "C_C") (pintype "passive"))
      (node (ref "PCA9685") (pin "8") (pinfunction "PWM2_8") (pintype "output"))
    )
    (net (code "72") (name "Net-(PCA9685-PWM3)") (class "Default")
      (node (ref "LED15") (pin "C") (pinfunction "C_C") (pintype "passive"))
      (node (ref "PCA9685") (pin "9") (pinfunction "PWM3_9") (pintype "output"))
    )
    (net (code "73") (name "Net-(PCA9685-PWM4)") (class "Default")
      (node (ref "LED16") (pin "C") (pinfunction "C_C") (pintype "passive"))
      (node (ref "PCA9685") (pin "10") (pinfunction "PWM4_10") (pintype "output"))
    )
    (net (code "74") (name "Net-(PCA9685-PWM5)") (class "Default")
      (node (ref "LED17") (pin "C") (pinfunction "C_C") (pintype "passive"))
      (node (ref "PCA9685") (pin "11") (pinfunction "PWM5_11") (pintype "output"))
    )
    (net (code "75") (name "Net-(PCA9685-PWM6)") (class "Default")
      (node (ref "LED18") (pin "C") (pinfunction "C_C") (pintype "passive"))
      (node (ref "PCA9685") (pin "12") (pinfunction "PWM6_12") (pintype "output"))
    )
    (net (code "76") (name "Net-(PCA9685-PWM7)") (class "Default")
      (node (ref "LED19") (pin "C") (pinfunction "C_C") (pintype "passive"))
      (node (ref "PCA9685") (pin "13") (pinfunction "PWM7_13") (pintype "output"))
    )
    (net (code "77") (name "Net-(PCA9685-PWM8)") (class "Default")
      (node (ref "LED20") (pin "C") (pinfunction "C_C") (pintype "passive"))
      (node (ref "PCA9685") (pin "15") (pinfunction "PWM8_15") (pintype "output"))
    )
    (net (code "78") (name "Net-(PCA9685-PWM9)") (class "Default")
      (node (ref "LED21") (pin "C") (pinfunction "C_C") (pintype "passive"))
      (node (ref "PCA9685") (pin "16") (pinfunction "PWM9_16") (pintype "output"))
    )
    (net (code "79") (name "Net-(PCA9685-PWM10)") (class "Default")
      (node (ref "LED22") (pin "C") (pinfunction "C_C") (pintype "passive"))
      (node (ref "PCA9685") (pin "17") (pinfunction "PWM10_17") (pintype "output"))
    )
    (net (code "80") (name "Net-(PCA9685-PWM11)") (class "Default")
      (node (ref "LED23") (pin "C") (pinfunction "C_C") (pintype "passive"))
      (node (ref "PCA9685") (pin "18") (pinfunction "PWM11_18") (pintype "output"))
    )
    (net (code "81") (name "Net-(PCA9685-PWM12)") (class "Default")
      (node (ref "LED24") (pin "C") (pinfunction "C_C") (pintype "passive"))
      (node (ref "PCA9685") (pin "19") (pinfunction "PWM12_19") (pintype "output"))
    )
    (net (code "82") (name "Net-(PCA9685-PWM13)") (class "Default")
      (node (ref "LED25") (pin "C") (pinfunction "C_C") (pintype "passive"))
      (node (ref "PCA9685") (pin "20") (pinfunction "PWM13_20") (pintype "output"))
    )
    (net (code "83") (name "Net-(PCA9685-PWM14)") (class "Default")
      (node (ref "LED26") (pin "C") (pinfunction "C_C") (pintype "passive"))
      (node (ref "PCA9685") (pin "21") (pinfunction "PWM14_21") (pintype "output"))
    )
    (net (code "84") (name "Net-(PCA9685-PWM15)") (class "Default")
      (node (ref "LED27") (pin "C") (pinfunction "C_C") (pintype "passive"))
      (node (ref "PCA9685") (pin "22") (pinfunction "PWM15_22") (pintype "output"))
    )
    (net (code "85") (name "Net-(R2-Pad2)") (class "Default")
      (node (ref "R2") (pin "2") (pinfunction "2_2") (pintype "passive"))
      (node (ref "X1") (pin "3") (pinfunction "3_3") (pintype "passive"))
    )
    (net (code "86") (name "Net-(R3-Pad2)") (class "Default")
      (node (ref "R3") (pin "2") (pinfunction "2_2") (pintype "passive"))
      (node (ref "X1") (pin "2") (pinfunction "2_2") (pintype "passive"))
    )
    (net (code "87") (name "Net-(S1-1)") (class "Default")
      (node (ref "R4") (pin "2") (pinfunction "2_2") (pintype "passive"))
      (node (ref "S1") (pin "P$1") (pinfunction "1_P$1") (pintype "passive"))
      (node (ref "U1") (pin "94") (pinfunction "BOOT0_94") (pintype "bidirectional"))
    )
    (net (code "88") (name "Net-(U$2-GN)") (class "Default")
      (node (ref "MAX7221") (pin "DIG0") (pinfunction "DIG0_DIG0") (pintype "bidirectional"))
      (node (ref "U$2") (pin "GND") (pinfunction "GN_GND") (pintype "bidirectional"))
      (node (ref "U$2") (pin "GND2") (pinfunction "GND_GND2") (pintype "bidirectional"))
    )
    (net (code "89") (name "Net-(U$3-GN)") (class "Default")
      (node (ref "MAX7221") (pin "DIG1") (pinfunction "DIG1_DIG1") (pintype "bidirectional"))
      (node (ref "U$3") (pin "GND") (pinfunction "GN_GND") (pintype "bidirectional"))
      (node (ref "U$3") (pin "GND2") (pinfunction "GND_GND2") (pintype "bidirectional"))
    )
    (net (code "90") (name "Net-(U$4-GN)") (class "Default")
      (node (ref "MAX7221") (pin "DIG2") (pinfunction "DIG2_DIG2") (pintype "bidirectional"))
      (node (ref "U$4") (pin "GND") (pinfunction "GN_GND") (pintype "bidirectional"))
      (node (ref "U$4") (pin "GND2") (pinfunction "GND_GND2") (pintype "bidirectional"))
    )
    (net (code "91") (name "Net-(U$5-GN)") (class "Default")
      (node (ref "MAX7221") (pin "DIG3") (pinfunction "DIG3_DIG3") (pintype "bidirectional"))
      (node (ref "U$5") (pin "GND") (pinfunction "GN_GND") (pintype "bidirectional"))
      (node (ref "U$5") (pin "GND2") (pinfunction "GND_GND2") (pintype "bidirectional"))
    )
    (net (code "92") (name "Net-(U$6-GN)") (class "Default")
      (node (ref "MAX7221") (pin "DIG4") (pinfunction "DIG4_DIG4") (pintype "bidirectional"))
      (node (ref "U$6") (pin "GND") (pinfunction "GN_GND") (pintype "bidirectional"))
      (node (ref "U$6") (pin "GND2") (pinfunction "GND_GND2") (pintype "bidirectional"))
    )
    (net (code "93") (name "Net-(U$7-GN)") (class "Default")
      (node (ref "MAX7221") (pin "DIG5") (pinfunction "DIG5_DIG5") (pintype "bidirectional"))
      (node (ref "U$7") (pin "GND") (pinfunction "GN_GND") (pintype "bidirectional"))
      (node (ref "U$7") (pin "GND2") (pinfunction "GND_GND2") (pintype "bidirectional"))
    )
    (net (code "94") (name "Net-(U$8-GN)") (class "Default")
      (node (ref "MAX7221") (pin "DIG6") (pinfunction "DIG6_DIG6") (pintype "bidirectional"))
      (node (ref "U$8") (pin "GND") (pinfunction "GN_GND") (pintype "bidirectional"))
      (node (ref "U$8") (pin "GND2") (pinfunction "GND_GND2") (pintype "bidirectional"))
    )
    (net (code "95") (name "Net-(U$10-OUT)") (class "Default")
      (node (ref "D2") (pin "C") (pinfunction "C_C") (pintype "passive"))
      (node (ref "L1") (pin "2") (pinfunction "2_2") (pintype "passive"))
      (node (ref "U$10") (pin "P$2") (pinfunction "OUT_P$2") (pintype "bidirectional"))
    )
    (net (code "96") (name "Net-(U1G-PH0)") (class "Default")
      (node (ref "C1") (pin "2") (pinfunction "2_2") (pintype "passive"))
      (node (ref "Q1") (pin "2") (pinfunction "2_2") (pintype "passive"))
      (node (ref "U1") (pin "12") (pinfunction "PH0_12") (pintype "bidirectional"))
    )
    (net (code "97") (name "Net-(U1G-PH1)") (class "Default")
      (node (ref "C2") (pin "2") (pinfunction "2_2") (pintype "passive"))
      (node (ref "Q1") (pin "1") (pinfunction "1_1") (pintype "passive"))
      (node (ref "U1") (pin "13") (pinfunction "PH1_13") (pintype "bidirectional"))
    )
    (net (code "98") (name "Net-(U2-IN1)") (class "Default")
      (node (ref "PAD1") (pin "3") (pinfunction "3_3") (pintype "passive"))
      (node (ref "U2") (pin "1") (pinfunction "IN1_1") (pintype "input"))
    )
    (net (code "99") (name "Net-(U2-IN2)") (class "Default")
      (node (ref "PAD1") (pin "2") (pinfunction "2_2") (pintype "passive"))
      (node (ref "U2") (pin "3") (pinfunction "IN2_3") (pintype "input"))
    )
    (net (code "100") (name "Net-(U3-IN1)") (class "Default")
      (node (ref "TC2") (pin "2") (pinfunction "2_2") (pintype "passive"))
      (node (ref "U3") (pin "1") (pinfunction "IN1_1") (pintype "input"))
    )
    (net (code "101") (name "Net-(U3-IN2)") (class "Default")
      (node (ref "TC1") (pin "2") (pinfunction "2_2") (pintype "passive"))
      (node (ref "U3") (pin "3") (pinfunction "IN2_3") (pintype "input"))
    )
    (net (code "102") (name "Net-(U4-IN1)") (class "Default")
      (node (ref "TC3") (pin "2") (pinfunction "2_2") (pintype "passive"))
      (node (ref "U4") (pin "1") (pinfunction "IN1_1") (pintype "input"))
    )
    (net (code "103") (name "Net-(U5-1Y)") (class "Default")
      (node (ref "MAX7221") (pin "DIN") (pinfunction "DIN_DIN") (pintype "bidirectional"))
      (node (ref "U5") (pin "2") (pinfunction "1Y_2") (pintype "bidirectional"))
    )
    (net (code "104") (name "Net-(U5-2Y)") (class "Default")
      (node (ref "MAX7221") (pin "CLK") (pinfunction "CLK_CLK") (pintype "bidirectional"))
      (node (ref "U5") (pin "4") (pinfunction "2Y_4") (pintype "bidirectional"))
    )
    (net (code "105") (name "Net-(U5-3Y)") (class "Default")
      (node (ref "MAX7221") (pin "LOAD") (pinfunction "LOAD_LOAD") (pintype "bidirectional"))
      (node (ref "U5") (pin "6") (pinfunction "3Y_6") (pintype "bidirectional"))
    )
    (net (code "106") (name "PADDOWN") (class "Default")
      (node (ref "U1") (pin "59") (pinfunction "PD12_59") (pintype "bidirectional"))
      (node (ref "U2") (pin "4") (pinfunction "OUT2_4") (pintype "output"))
    )
    (net (code "107") (name "PADUP") (class "Default")
      (node (ref "U1") (pin "58") (pinfunction "PD11_58") (pintype "bidirectional"))
      (node (ref "U2") (pin "6") (pinfunction "OUT1_6") (pintype "output"))
    )
    (net (code "108") (name "RESET") (class "Default")
      (node (ref "JTAG1") (pin "15") (pinfunction "15_15") (pintype "passive"))
      (node (ref "R5") (pin "1") (pinfunction "1_1") (pintype "passive"))
      (node (ref "S2") (pin "P$1") (pinfunction "1_P$1") (pintype "passive"))
      (node (ref "U1") (pin "14") (pinfunction "NRST_14") (pintype "bidirectional"))
    )
    (net (code "109") (name "ROTSW1") (class "Default")
      (node (ref "R16") (pin "2") (pinfunction "2_2") (pintype "passive"))
      (node (ref "ROT1") (pin "6") (pinfunction "6_6") (pintype "passive"))
      (node (ref "U1") (pin "29") (pinfunction "PA4_29") (pintype "bidirectional"))
    )
    (net (code "110") (name "ROTSW2") (class "Default")
      (node (ref "R15") (pin "2") (pinfunction "2_2") (pintype "passive"))
      (node (ref "ROT1") (pin "5") (pinfunction "5_5") (pintype "passive"))
      (node (ref "U1") (pin "30") (pinfunction "PA5_30") (pintype "bidirectional"))
    )
    (net (code "111") (name "ROTSW3") (class "Default")
      (node (ref "R14") (pin "2") (pinfunction "2_2") (pintype "passive"))
      (node (ref "ROT1") (pin "4") (pinfunction "4_4") (pintype "passive"))
      (node (ref "U1") (pin "31") (pinfunction "PA6_31") (pintype "bidirectional"))
    )
    (net (code "112") (name "ROTSW4") (class "Default")
      (node (ref "R13") (pin "2") (pinfunction "2_2") (pintype "passive"))
      (node (ref "ROT1") (pin "3") (pinfunction "3_3") (pintype "passive"))
      (node (ref "U1") (pin "32") (pinfunction "PA7_32") (pintype "bidirectional"))
    )
    (net (code "113") (name "SCL") (class "Default")
      (node (ref "PCA9685") (pin "26") (pinfunction "SCL_26") (pintype "bidirectional"))
      (node (ref "PCA9685-1") (pin "26") (pinfunction "SCL_26") (pintype "bidirectional"))
      (node (ref "R18") (pin "1") (pinfunction "1_1") (pintype "passive"))
      (node (ref "U$38") (pin "26") (pinfunction "SCL_26") (pintype "bidirectional"))
      (node (ref "U1") (pin "92") (pinfunction "PB6_92") (pintype "bidirectional"))
    )
    (net (code "114") (name "SDA") (class "Default")
      (node (ref "PCA9685") (pin "27") (pinfunction "SDA_27") (pintype "bidirectional"))
      (node (ref "PCA9685-1") (pin "27") (pinfunction "SDA_27") (pintype "bidirectional"))
      (node (ref "R17") (pin "1") (pinfunction "1_1") (pintype "passive"))
      (node (ref "U$38") (pin "27") (pinfunction "SDA_27") (pintype "bidirectional"))
      (node (ref "U1") (pin "93") (pinfunction "PB7_93") (pintype "bidirectional"))
    )
    (net (code "115") (name "SLBLUE") (class "Default")
      (node (ref "R29") (pin "2") (pinfunction "2_2") (pintype "passive"))
      (node (ref "U1") (pin "40") (pinfunction "PE9_40") (pintype "bidirectional"))
    )
    (net (code "116") (name "SLGREEN") (class "Default")
      (node (ref "R19") (pin "2") (pinfunction "2_2") (pintype "passive"))
      (node (ref "U1") (pin "42") (pinfunction "PE11_42") (pintype "bidirectional"))
    )
    (net (code "117") (name "SLRED") (class "Default")
      (node (ref "R6") (pin "2") (pinfunction "2_2") (pintype "passive"))
      (node (ref "U1") (pin "44") (pinfunction "PE13_44") (pintype "bidirectional"))
    )
    (net (code "118") (name "SPI-LOAD") (class "Default")
      (node (ref "U1") (pin "51") (pinfunction "PB12_51") (pintype "bidirectional"))
      (node (ref "U5") (pin "7") (pinfunction "3A_7") (pintype "bidirectional"))
    )
    (net (code "119") (name "SPI-MISO") (class "Default")
      (node (ref "U1") (pin "53") (pinfunction "PB14_53") (pintype "bidirectional"))
    )
    (net (code "120") (name "SPI-MOSI") (class "Default")
      (node (ref "U1") (pin "54") (pinfunction "PB15_54") (pintype "bidirectional"))
      (node (ref "U5") (pin "3") (pinfunction "1A_3") (pintype "bidirectional"))
    )
    (net (code "121") (name "SPI-SCK") (class "Default")
      (node (ref "U1") (pin "52") (pinfunction "PB13_52") (pintype "bidirectional"))
      (node (ref "U5") (pin "5") (pinfunction "2A_5") (pintype "bidirectional"))
    )
    (net (code "122") (name "TCTEMPOFF") (class "Default")
      (node (ref "U1") (pin "33") (pinfunction "PC4_33") (pintype "bidirectional"))
      (node (ref "U4") (pin "6") (pinfunction "OUT1_6") (pintype "output"))
    )
    (net (code "123") (name "USB_DM") (class "Default")
      (node (ref "R3") (pin "1") (pinfunction "1_1") (pintype "passive"))
      (node (ref "U1") (pin "70") (pinfunction "PA11_70") (pintype "bidirectional"))
    )
    (net (code "124") (name "USB_DP") (class "Default")
      (node (ref "R2") (pin "1") (pinfunction "1_1") (pintype "passive"))
      (node (ref "U1") (pin "71") (pinfunction "PA12_71") (pintype "bidirectional"))
    )
    (net (code "125") (name "USB_ID") (class "Default")
      (node (ref "U1") (pin "69") (pinfunction "PA10_69") (pintype "bidirectional"))
      (node (ref "X1") (pin "4") (pinfunction "4_4") (pintype "passive"))
    )
    (net (code "126") (name "USB_VBUS") (class "Default")
      (node (ref "C26") (pin "1") (pinfunction "1_1") (pintype "passive"))
      (node (ref "U1") (pin "68") (pinfunction "PA9_68") (pintype "bidirectional"))
      (node (ref "X1") (pin "1") (pinfunction "1_1") (pintype "passive"))
    )
    (net (code "127") (name "unconnected-(IC3-VREF-Pad5)") (class "Default")
      (node (ref "IC3") (pin "5") (pinfunction "VREF_5") (pintype "output"))
    )
    (net (code "128") (name "unconnected-(JTAG1-Pad11)") (class "Default")
      (node (ref "JTAG1") (pin "11") (pinfunction "11_11") (pintype "passive"))
    )
    (net (code "129") (name "unconnected-(JTAG1-Pad17)") (class "Default")
      (node (ref "JTAG1") (pin "17") (pinfunction "17_17") (pintype "passive"))
    )
    (net (code "130") (name "unconnected-(JTAG1-Pad19)") (class "Default")
      (node (ref "JTAG1") (pin "19") (pinfunction "19_19") (pintype "passive"))
    )
    (net (code "131") (name "unconnected-(MAX7221-PadDIG7)") (class "Default")
      (node (ref "MAX7221") (pin "DIG7") (pinfunction "DIG7_DIG7") (pintype "bidirectional"))
    )
    (net (code "132") (name "unconnected-(MAX7221-PadDOUT)") (class "Default")
      (node (ref "MAX7221") (pin "DOUT") (pinfunction "DOUT_DOUT") (pintype "bidirectional"))
    )
    (net (code "133") (name "unconnected-(PCA9685-1-PWM15-Pad22)") (class "Default")
      (node (ref "PCA9685-1") (pin "22") (pinfunction "PWM15_22") (pintype "output"))
    )
    (net (code "134") (name "unconnected-(U$38-A0-Pad2)") (class "Default")
      (node (ref "U$38") (pin "2") (pinfunction "A0_2") (pintype "bidirectional"))
    )
    (net (code "135") (name "unconnected-(U$38-A1-Pad3)") (class "Default")
      (node (ref "U$38") (pin "3") (pinfunction "A1_3") (pintype "bidirectional"))
    )
    (net (code "136") (name "unconnected-(U$38-A2-Pad4)") (class "Default")
      (node (ref "U$38") (pin "4") (pinfunction "A2_4") (pintype "bidirectional"))
    )
    (net (code "137") (name "unconnected-(U$38-A3-Pad5)") (class "Default")
      (node (ref "U$38") (pin "5") (pinfunction "A3_5") (pintype "bidirectional"))
    )
    (net (code "138") (name "unconnected-(U$38-REXT-Pad1)") (class "Default")
      (node (ref "U$38") (pin "1") (pinfunction "REXT_1") (pintype "bidirectional"))
    )
    (net (code "139") (name "unconnected-(U$38-{slash}OUT15-Pad23)") (class "Default")
      (node (ref "U$38") (pin "23") (pinfunction "/OUT15_23") (pintype "bidirectional"))
    )
    (net (code "140") (name "unconnected-(U$38-{slash}RESET-Pad25)") (class "Default")
      (node (ref "U$38") (pin "25") (pinfunction "/RESET_25") (pintype "bidirectional"))
    )
    (net (code "141") (name "unconnected-(U1B-PA0-Pad23)") (class "Default")
      (node (ref "U1") (pin "23") (pinfunction "PA0_23") (pintype "bidirectional"))
    )
    (net (code "142") (name "unconnected-(U1B-PA1-Pad24)") (class "Default")
      (node (ref "U1") (pin "24") (pinfunction "PA1_24") (pintype "bidirectional"))
    )
    (net (code "143") (name "unconnected-(U1B-PA2-Pad25)") (class "Default")
      (node (ref "U1") (pin "25") (pinfunction "PA2_25") (pintype "bidirectional"))
    )
    (net (code "144") (name "unconnected-(U1B-PA3-Pad26)") (class "Default")
      (node (ref "U1") (pin "26") (pinfunction "PA3_26") (pintype "bidirectional"))
    )
    (net (code "145") (name "unconnected-(U1B-PA8-Pad67)") (class "Default")
      (node (ref "U1") (pin "67") (pinfunction "PA8_67") (pintype "bidirectional"))
    )
    (net (code "146") (name "unconnected-(U1C-PB0-Pad35)") (class "Default")
      (node (ref "U1") (pin "35") (pinfunction "PB0_35") (pintype "bidirectional"))
    )
    (net (code "147") (name "unconnected-(U1C-PB1-Pad36)") (class "Default")
      (node (ref "U1") (pin "36") (pinfunction "PB1_36") (pintype "bidirectional"))
    )
    (net (code "148") (name "unconnected-(U1C-PB4-Pad90)") (class "Default")
      (node (ref "U1") (pin "90") (pinfunction "PB4_90") (pintype "bidirectional"))
    )
    (net (code "149") (name "unconnected-(U1C-PB5-Pad91)") (class "Default")
      (node (ref "U1") (pin "91") (pinfunction "PB5_91") (pintype "bidirectional"))
    )
    (net (code "150") (name "unconnected-(U1C-PB10-Pad47)") (class "Default")
      (node (ref "U1") (pin "47") (pinfunction "PB10_47") (pintype "bidirectional"))
    )
    (net (code "151") (name "unconnected-(U1C-PB11-Pad48)") (class "Default")
      (node (ref "U1") (pin "48") (pinfunction "PB11_48") (pintype "bidirectional"))
    )
    (net (code "152") (name "unconnected-(U1D-PC0-Pad15)") (class "Default")
      (node (ref "U1") (pin "15") (pinfunction "PC0_15") (pintype "bidirectional"))
    )
    (net (code "153") (name "unconnected-(U1D-PC1-Pad16)") (class "Default")
      (node (ref "U1") (pin "16") (pinfunction "PC1_16") (pintype "bidirectional"))
    )
    (net (code "154") (name "unconnected-(U1D-PC2-Pad17)") (class "Default")
      (node (ref "U1") (pin "17") (pinfunction "PC2_17") (pintype "bidirectional"))
    )
    (net (code "155") (name "unconnected-(U1D-PC3-Pad18)") (class "Default")
      (node (ref "U1") (pin "18") (pinfunction "PC3_18") (pintype "bidirectional"))
    )
    (net (code "156") (name "unconnected-(U1D-PC5-Pad34)") (class "Default")
      (node (ref "U1") (pin "34") (pinfunction "PC5_34") (pintype "bidirectional"))
    )
    (net (code "157") (name "unconnected-(U1D-PC6-Pad63)") (class "Default")
      (node (ref "U1") (pin "63") (pinfunction "PC6_63") (pintype "bidirectional"))
    )
    (net (code "158") (name "unconnected-(U1D-PC7-Pad64)") (class "Default")
      (node (ref "U1") (pin "64") (pinfunction "PC7_64") (pintype "bidirectional"))
    )
    (net (code "159") (name "unconnected-(U1D-PC8-Pad65)") (class "Default")
      (node (ref "U1") (pin "65") (pinfunction "PC8_65") (pintype "bidirectional"))
    )
    (net (code "160") (name "unconnected-(U1D-PC9-Pad66)") (class "Default")
      (node (ref "U1") (pin "66") (pinfunction "PC9_66") (pintype "bidirectional"))
    )
    (net (code "161") (name "unconnected-(U1D-PC10-Pad78)") (class "Default")
      (node (ref "U1") (pin "78") (pinfunction "PC10_78") (pintype "bidirectional"))
    )
    (net (code "162") (name "unconnected-(U1D-PC11-Pad79)") (class "Default")
      (node (ref "U1") (pin "79") (pinfunction "PC11_79") (pintype "bidirectional"))
    )
    (net (code "163") (name "unconnected-(U1D-PC12-Pad80)") (class "Default")
      (node (ref "U1") (pin "80") (pinfunction "PC12_80") (pintype "bidirectional"))
    )
    (net (code "164") (name "unconnected-(U1D-PC13-Pad7)") (class "Default")
      (node (ref "U1") (pin "7") (pinfunction "PC13_7") (pintype "bidirectional"))
    )
    (net (code "165") (name "unconnected-(U1D-PC14-Pad8)") (class "Default")
      (node (ref "U1") (pin "8") (pinfunction "PC14_8") (pintype "bidirectional"))
    )
    (net (code "166") (name "unconnected-(U1D-PC15-Pad9)") (class "Default")
      (node (ref "U1") (pin "9") (pinfunction "PC15_9") (pintype "bidirectional"))
    )
    (net (code "167") (name "unconnected-(U1E-PD8-Pad55)") (class "Default")
      (node (ref "U1") (pin "55") (pinfunction "PD8_55") (pintype "bidirectional"))
    )
    (net (code "168") (name "unconnected-(U1E-PD13-Pad60)") (class "Default")
      (node (ref "U1") (pin "60") (pinfunction "PD13_60") (pintype "bidirectional"))
    )
    (net (code "169") (name "unconnected-(U1E-PD14-Pad61)") (class "Default")
      (node (ref "U1") (pin "61") (pinfunction "PD14_61") (pintype "bidirectional"))
    )
    (net (code "170") (name "unconnected-(U1E-PD15-Pad62)") (class "Default")
      (node (ref "U1") (pin "62") (pinfunction "PD15_62") (pintype "bidirectional"))
    )
    (net (code "171") (name "unconnected-(U1F-PE0-Pad97)") (class "Default")
      (node (ref "U1") (pin "97") (pinfunction "PE0_97") (pintype "bidirectional"))
    )
    (net (code "172") (name "unconnected-(U1F-PE1-Pad98)") (class "Default")
      (node (ref "U1") (pin "98") (pinfunction "PE1_98") (pintype "bidirectional"))
    )
    (net (code "173") (name "unconnected-(U1F-PE2-Pad1)") (class "Default")
      (node (ref "U1") (pin "1") (pinfunction "PE2_1") (pintype "bidirectional"))
    )
    (net (code "174") (name "unconnected-(U1F-PE3-Pad2)") (class "Default")
      (node (ref "U1") (pin "2") (pinfunction "PE3_2") (pintype "bidirectional"))
    )
    (net (code "175") (name "unconnected-(U1F-PE4-Pad3)") (class "Default")
      (node (ref "U1") (pin "3") (pinfunction "PE4_3") (pintype "bidirectional"))
    )
    (net (code "176") (name "unconnected-(U1F-PE5-Pad4)") (class "Default")
      (node (ref "U1") (pin "4") (pinfunction "PE5_4") (pintype "bidirectional"))
    )
    (net (code "177") (name "unconnected-(U1F-PE6-Pad5)") (class "Default")
      (node (ref "U1") (pin "5") (pinfunction "PE6_5") (pintype "bidirectional"))
    )
    (net (code "178") (name "unconnected-(U1F-PE7-Pad38)") (class "Default")
      (node (ref "U1") (pin "38") (pinfunction "PE7_38") (pintype "bidirectional"))
    )
    (net (code "179") (name "unconnected-(U1F-PE8-Pad39)") (class "Default")
      (node (ref "U1") (pin "39") (pinfunction "PE8_39") (pintype "bidirectional"))
    )
    (net (code "180") (name "unconnected-(U1F-PE10-Pad41)") (class "Default")
      (node (ref "U1") (pin "41") (pinfunction "PE10_41") (pintype "bidirectional"))
    )
    (net (code "181") (name "unconnected-(U1F-PE12-Pad43)") (class "Default")
      (node (ref "U1") (pin "43") (pinfunction "PE12_43") (pintype "bidirectional"))
    )
    (net (code "182") (name "unconnected-(U1F-PE14-Pad45)") (class "Default")
      (node (ref "U1") (pin "45") (pinfunction "PE14_45") (pintype "bidirectional"))
    )
    (net (code "183") (name "unconnected-(U1F-PE15-Pad46)") (class "Default")
      (node (ref "U1") (pin "46") (pinfunction "PE15_46") (pintype "bidirectional"))
    )
    (net (code "184") (name "unconnected-(U4-IN2-Pad3)") (class "Default")
      (node (ref "U4") (pin "3") (pinfunction "IN2_3") (pintype "input"))
    )
    (net (code "185") (name "unconnected-(U4-OUT2-Pad4)") (class "Default")
      (node (ref "U4") (pin "4") (pinfunction "OUT2_4") (pintype "output"))
    )
    (net (code "186") (name "unconnected-(U5-4A-Pad9)") (class "Default")
      (node (ref "U5") (pin "9") (pinfunction "4A_9") (pintype "bidirectional"))
    )
    (net (code "187") (name "unconnected-(U5-4Y-Pad10)") (class "Default")
      (node (ref "U5") (pin "10") (pinfunction "4Y_10") (pintype "bidirectional"))
    )
    (net (code "188") (name "unconnected-(U5-5A-Pad11)") (class "Default")
      (node (ref "U5") (pin "11") (pinfunction "5A_11") (pintype "bidirectional"))
    )
    (net (code "189") (name "unconnected-(U5-5Y-Pad12)") (class "Default")
      (node (ref "U5") (pin "12") (pinfunction "5Y_12") (pintype "bidirectional"))
    )
    (net (code "190") (name "unconnected-(U5-6A-Pad14)") (class "Default")
      (node (ref "U5") (pin "14") (pinfunction "6A_14") (pintype "bidirectional"))
    )
    (net (code "191") (name "unconnected-(U5-6Y-Pad15)") (class "Default")
      (node (ref "U5") (pin "15") (pinfunction "6Y_15") (pintype "bidirectional"))
    )
  )
)
